# Tortilla.net
KiCad netlist of a schematic drawn in EAGLE
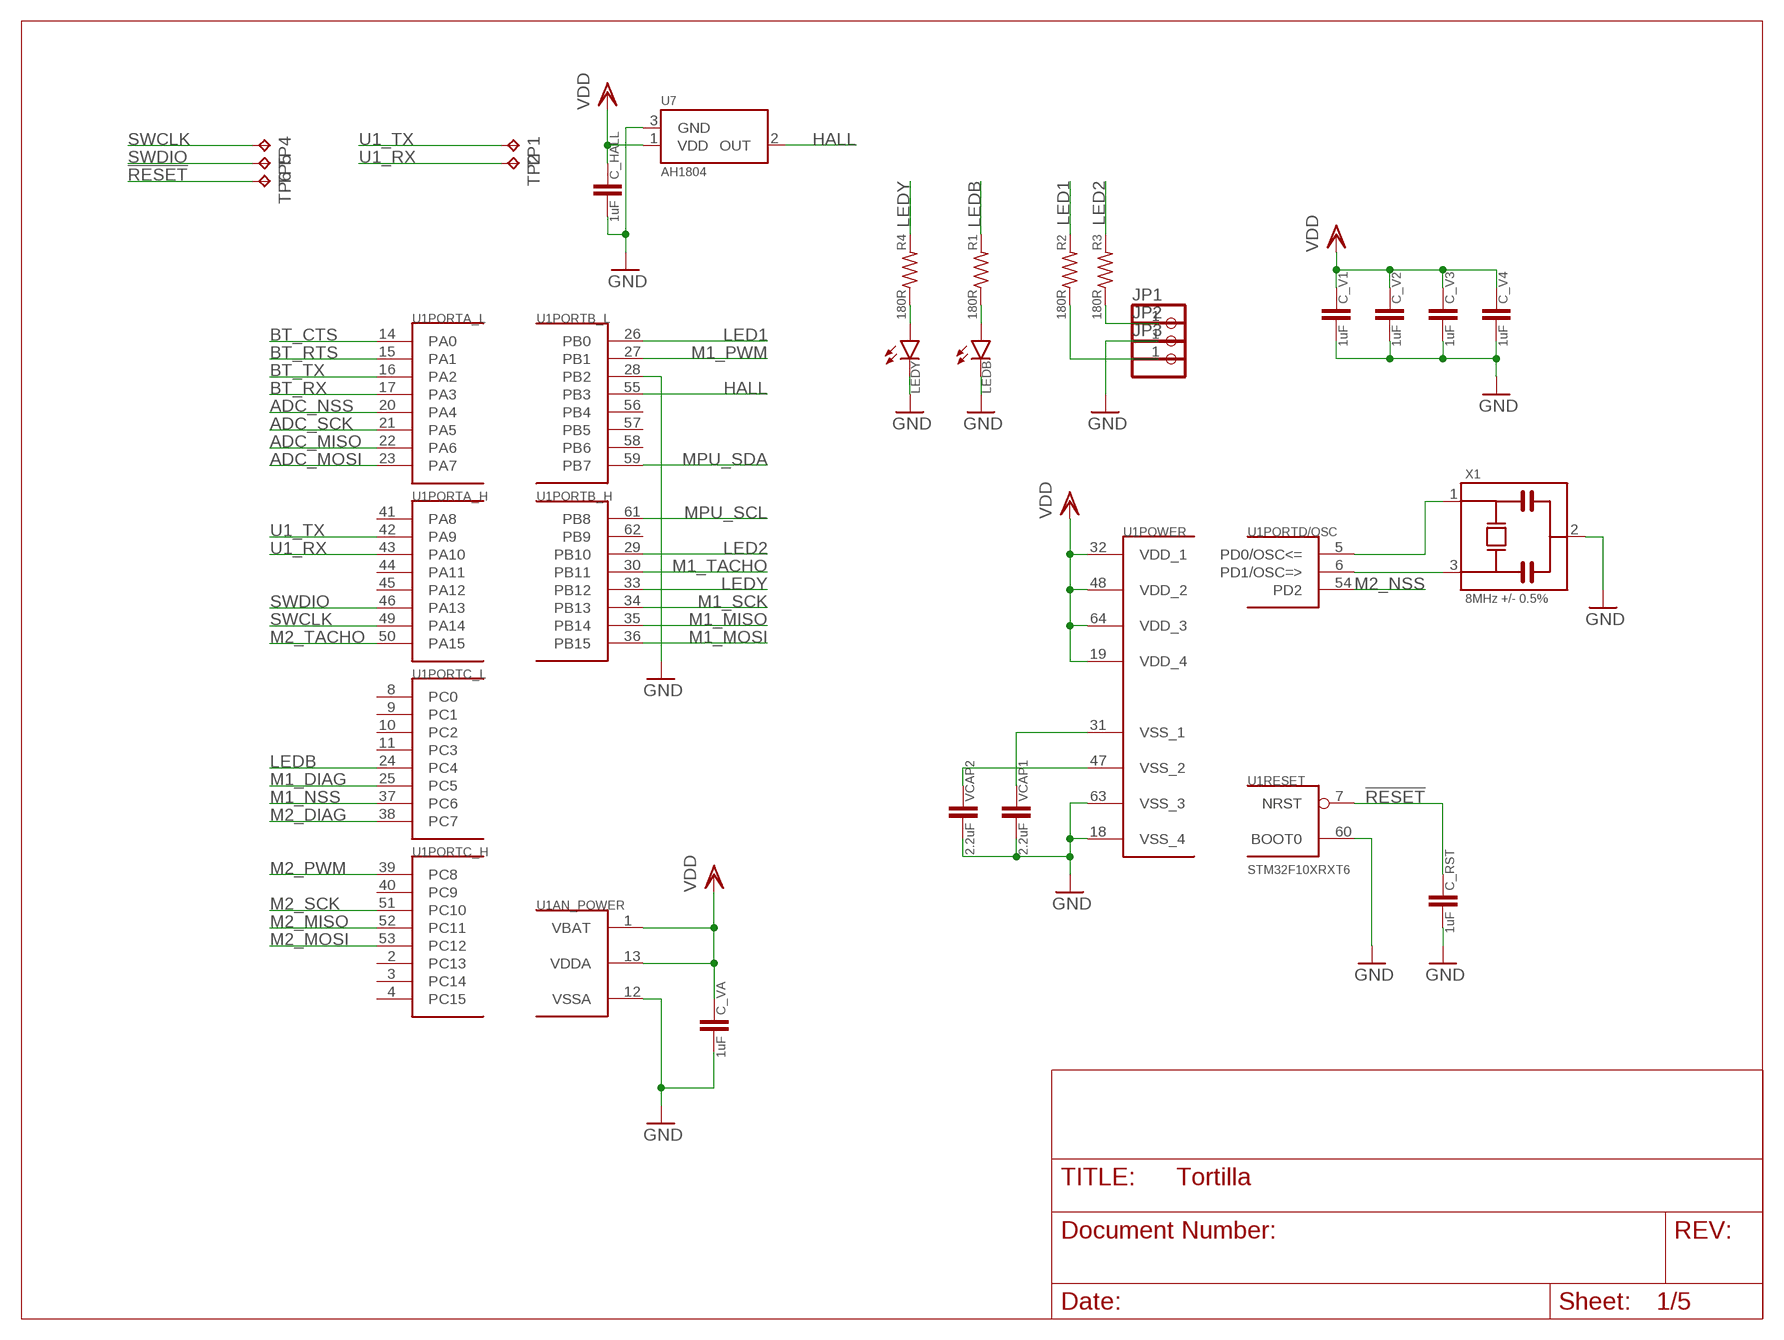
[diagram p0: schematic, sheet 1]
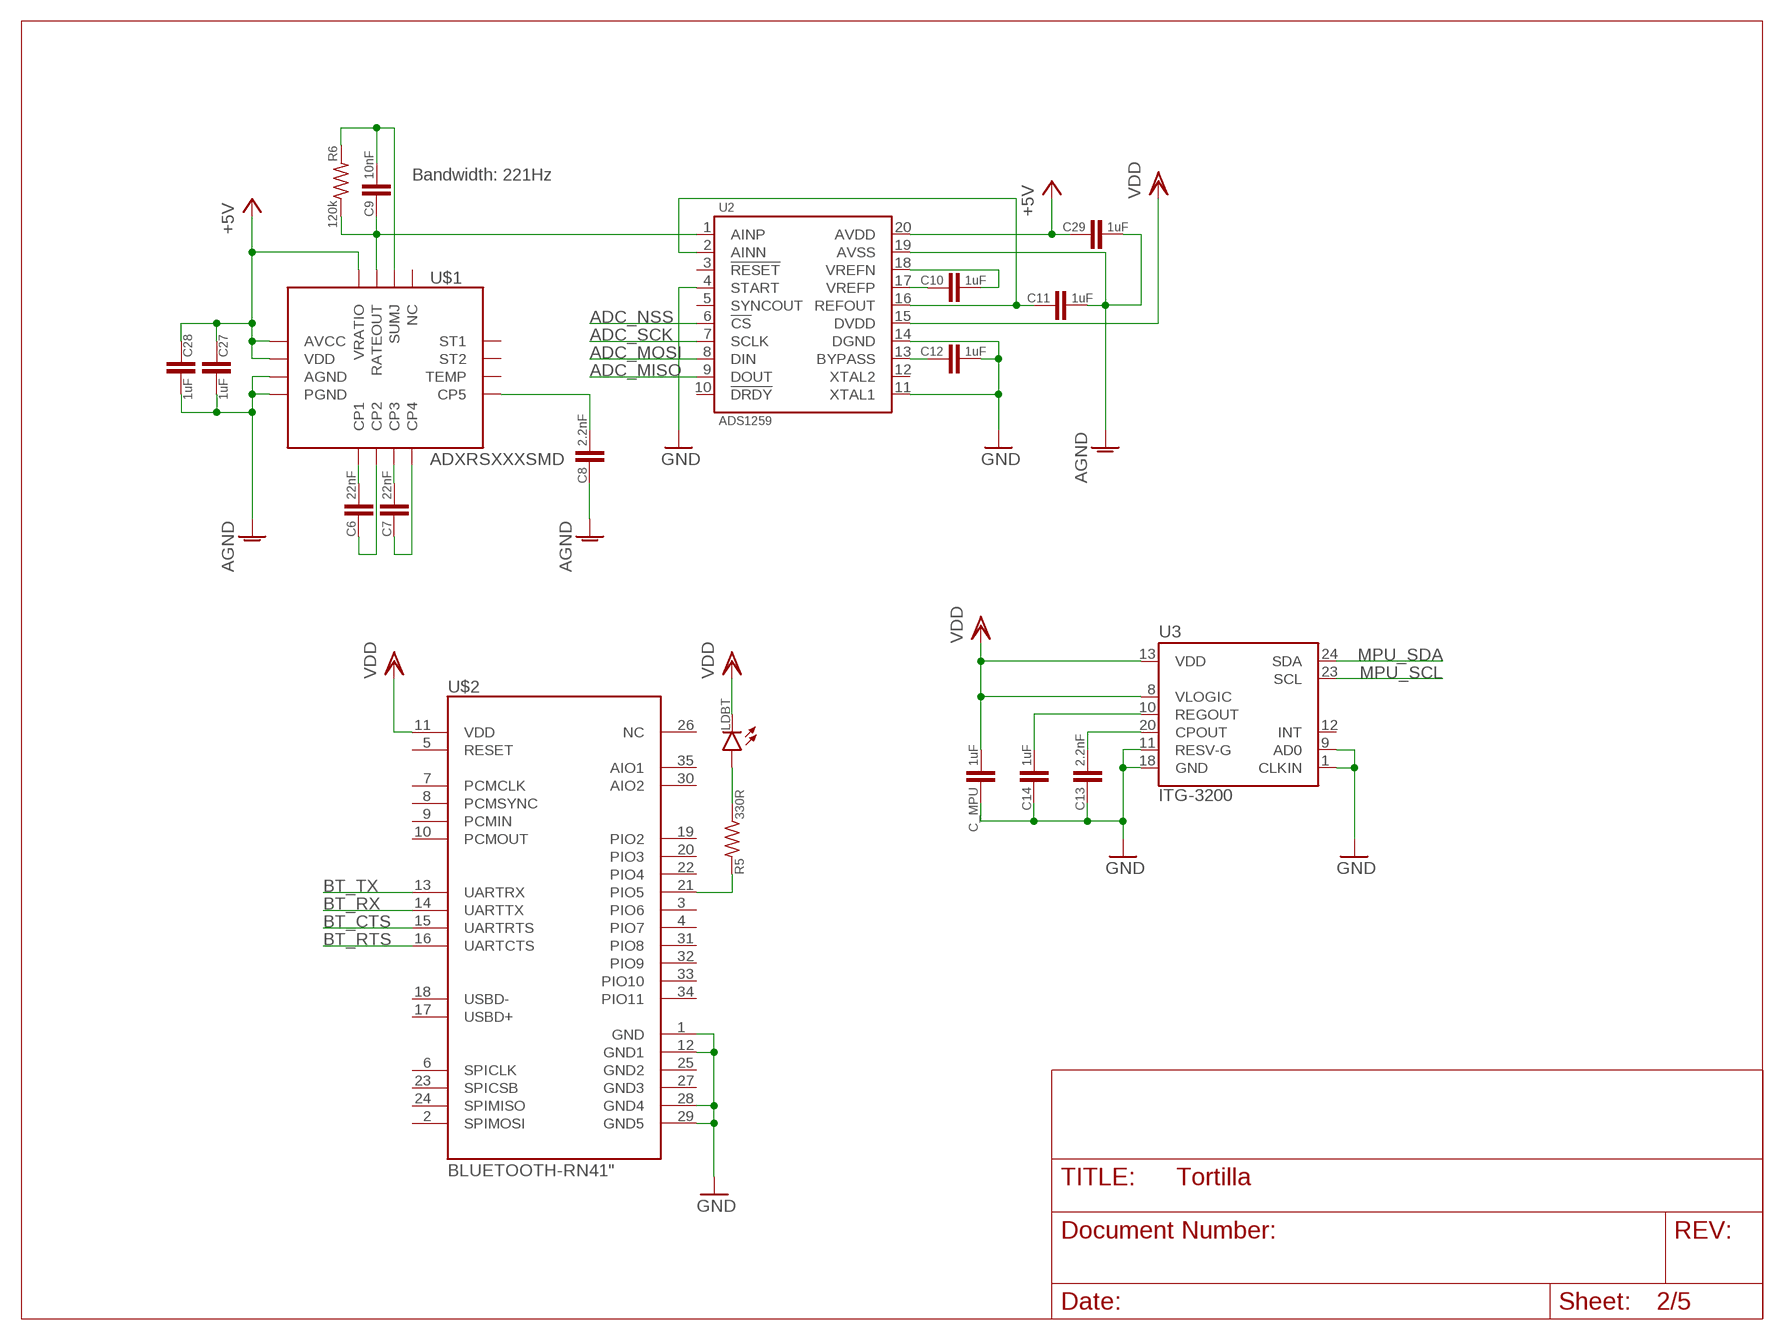
[diagram p1: schematic, sheet 2]
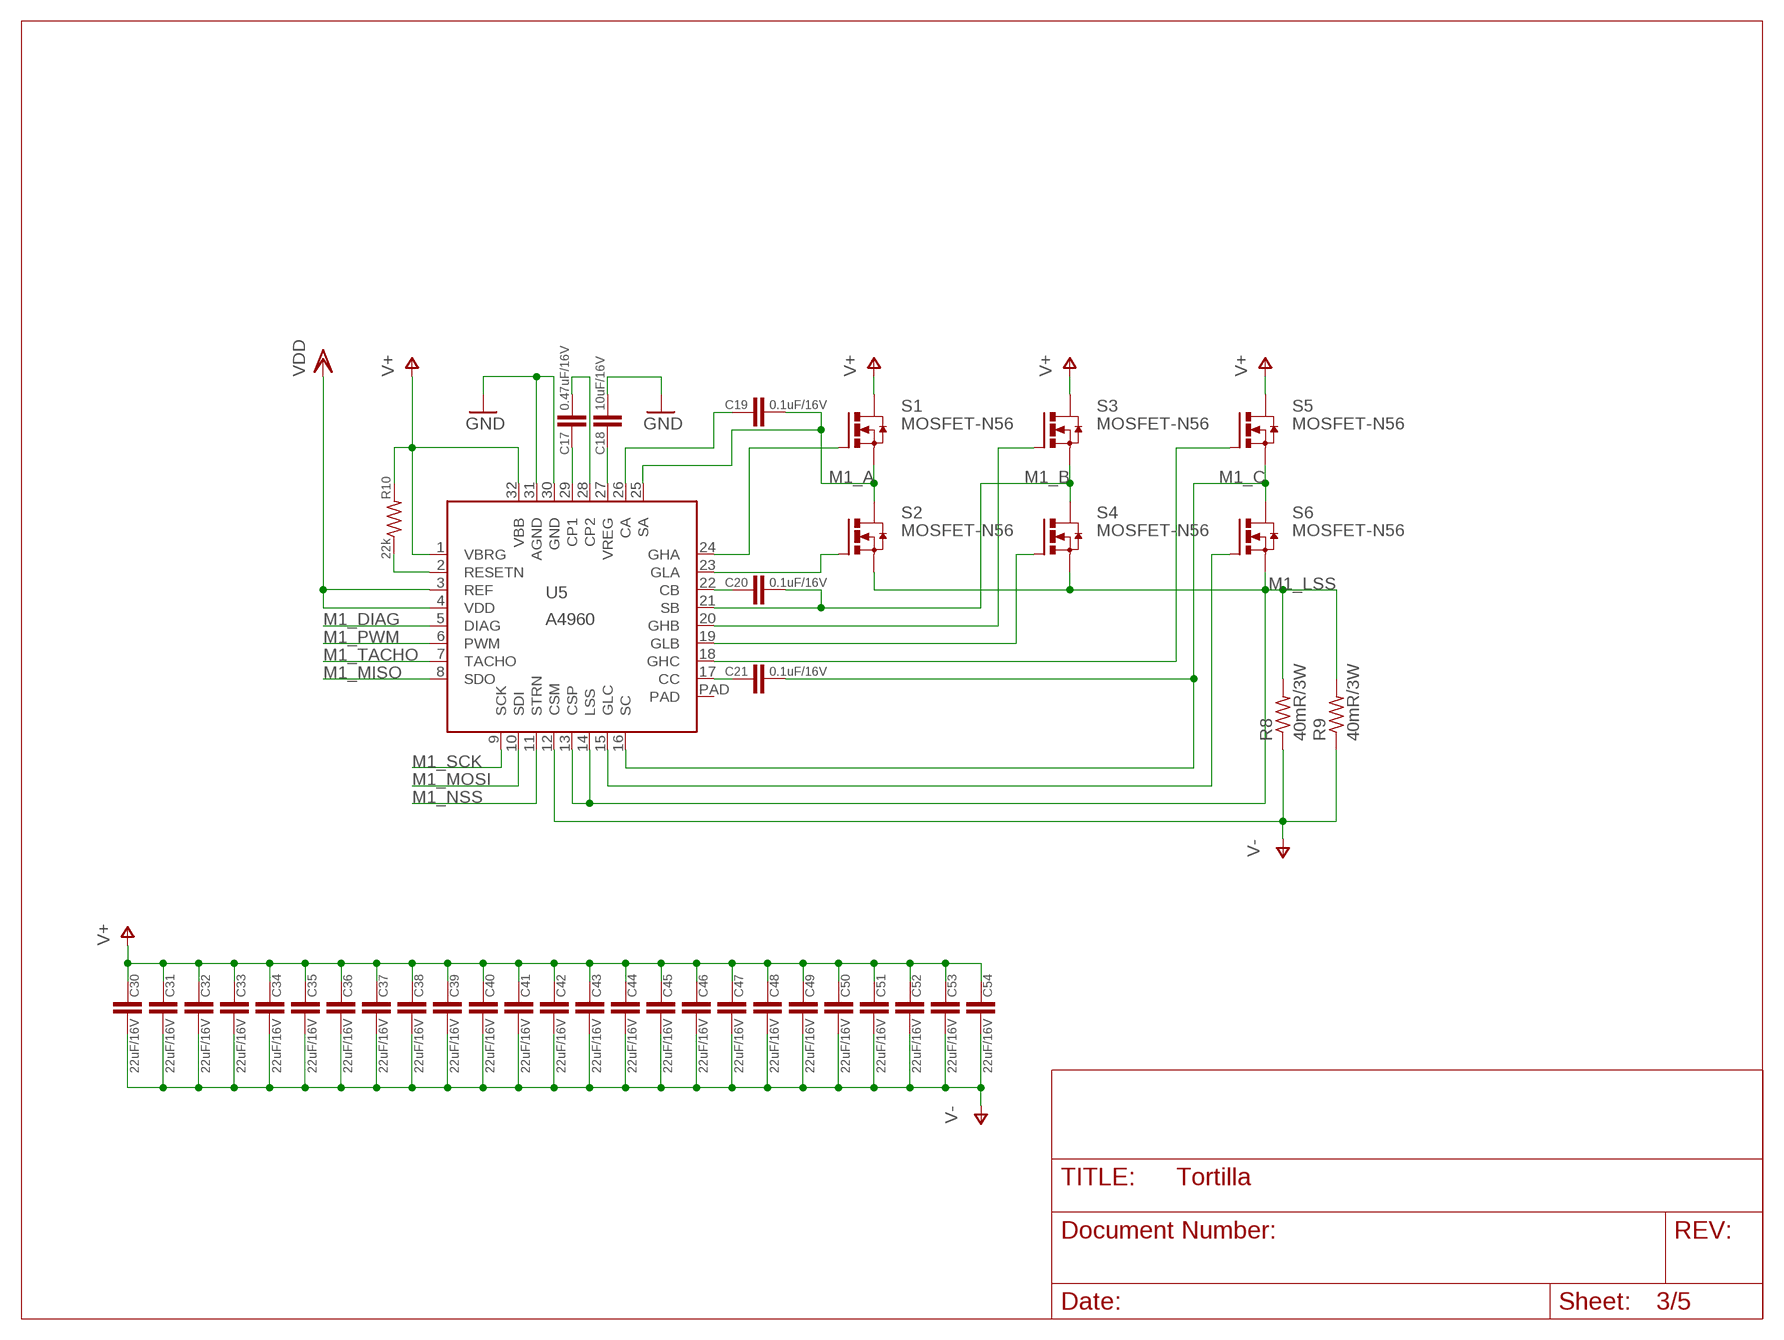
[diagram p2: schematic, sheet 3]
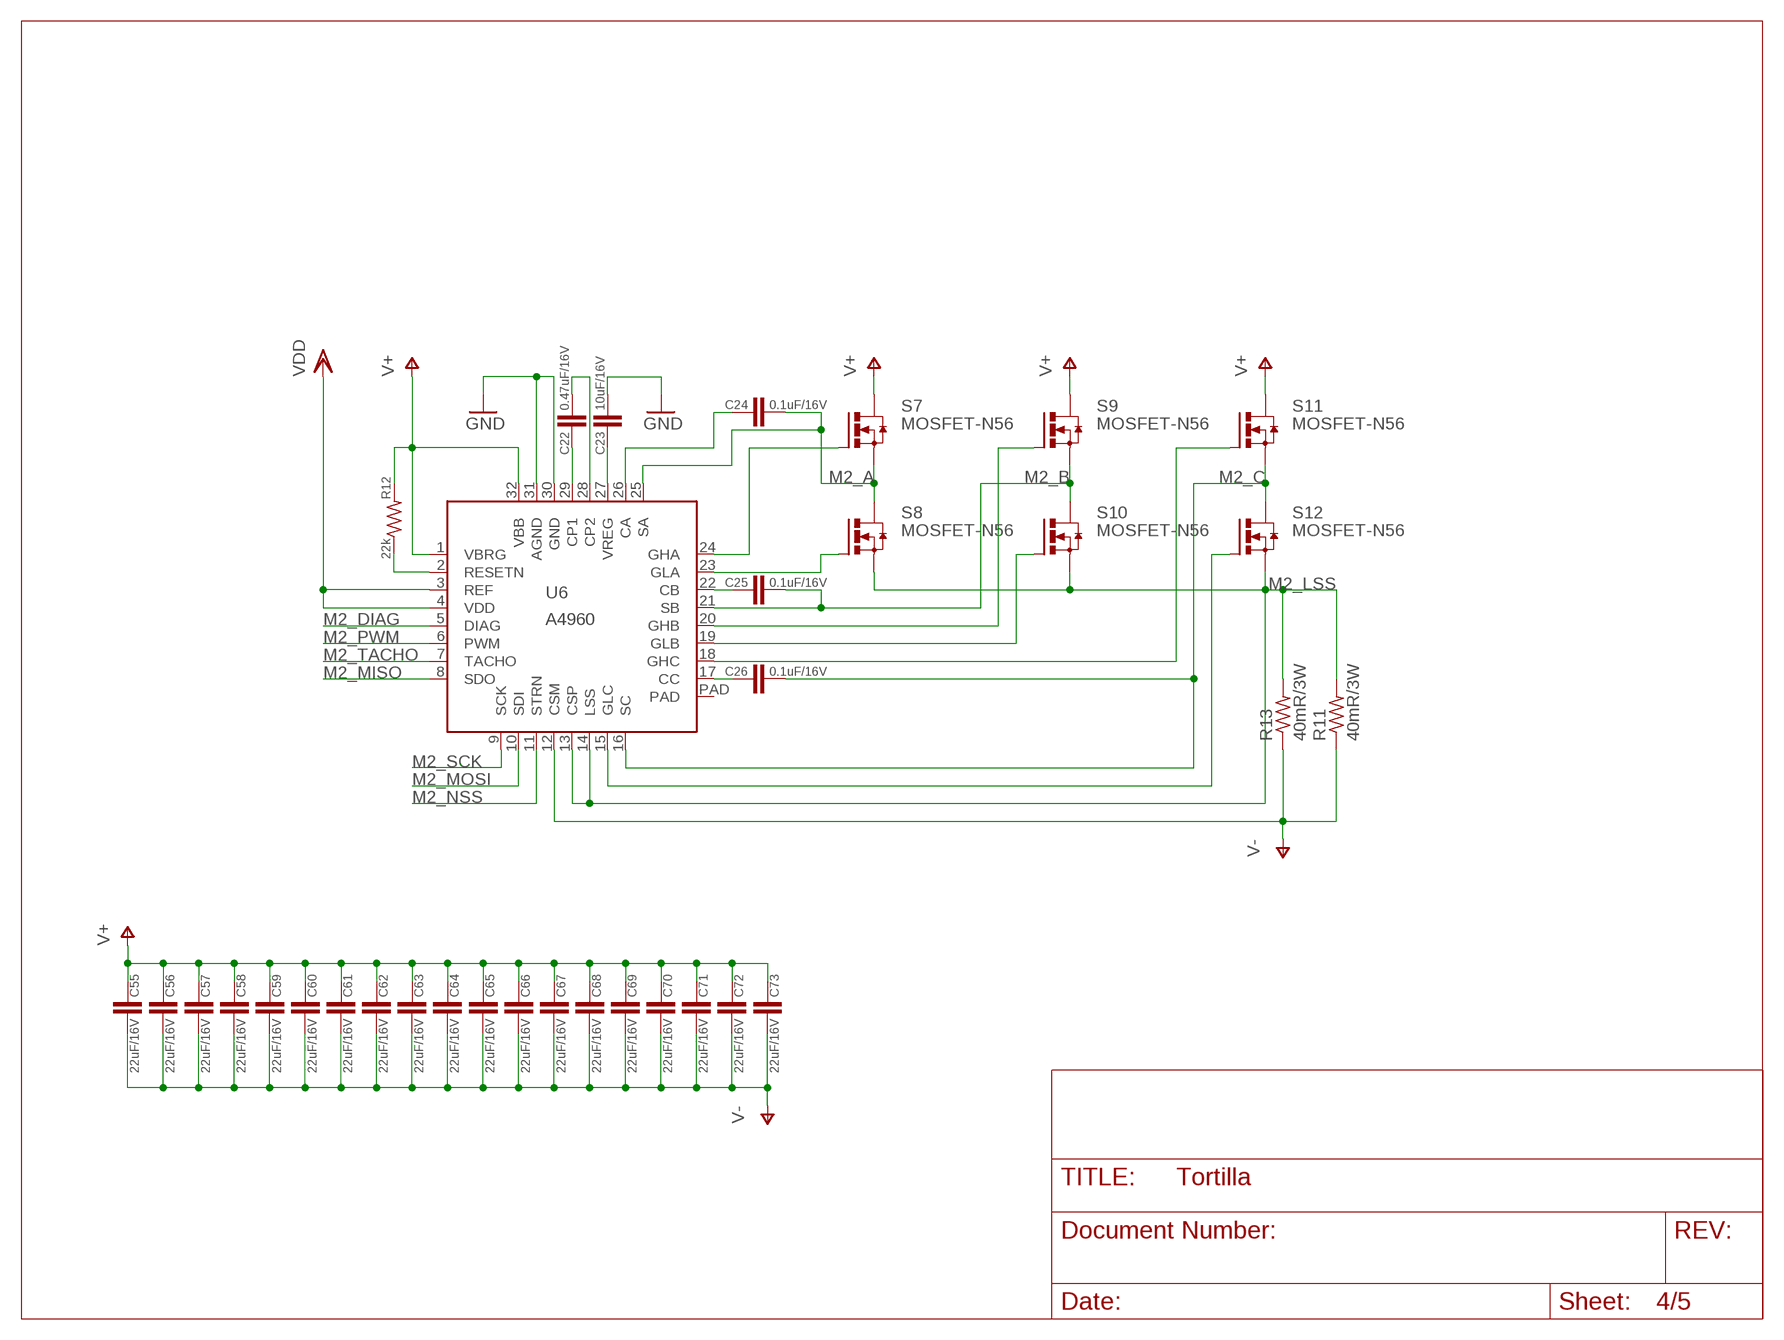
[diagram p3: schematic, sheet 4]
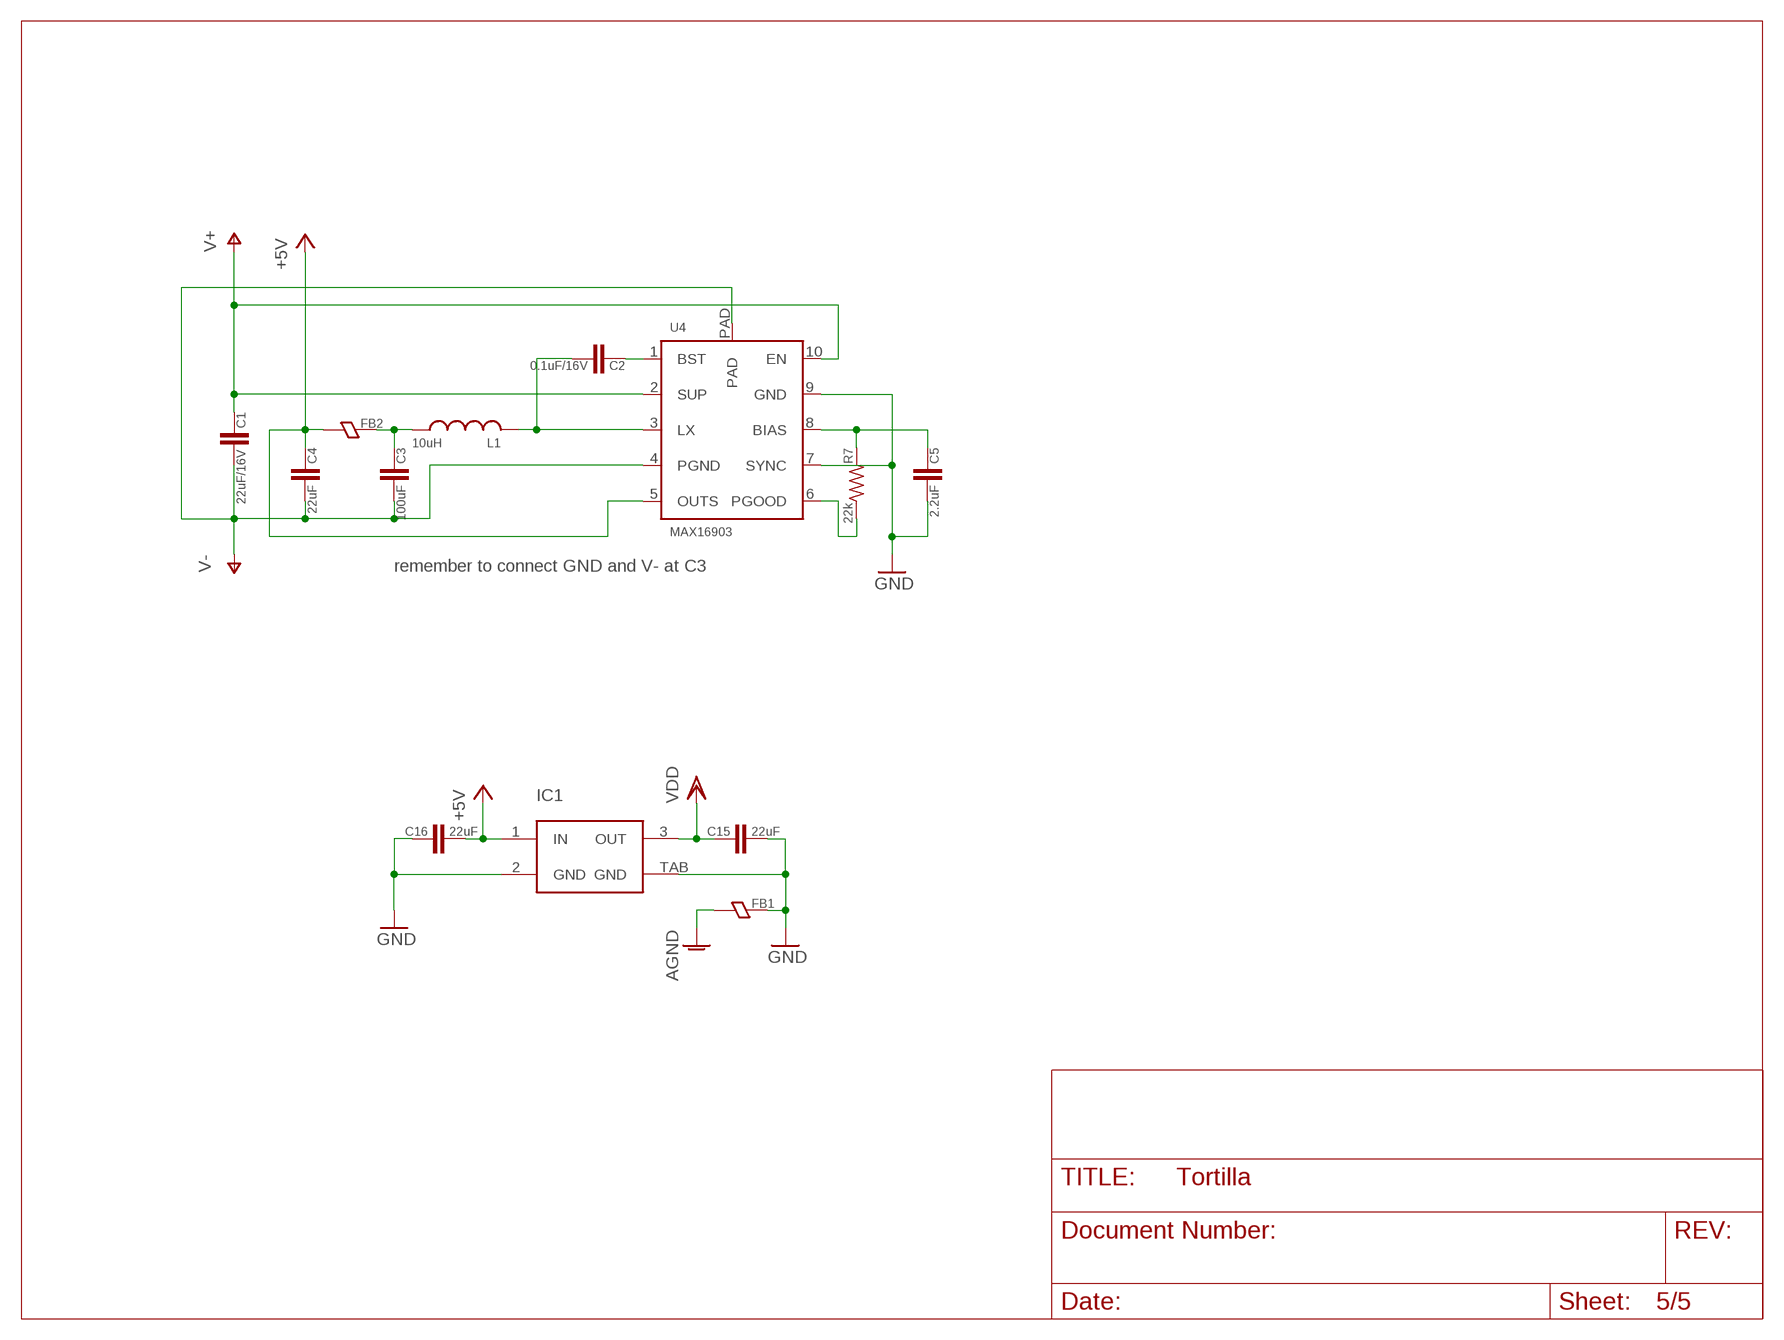
[diagram p4: schematic, sheet 5]

(export (version "E")
  (design (tool "Eeschema 10.0.6"))
  (components
    (comp (ref "C1")
      (value "22uF/16V")
      (footprint "eagle-import:0805")
      (libsource (lib "eagle-import") (part "C0805"))
    )
    (comp (ref "C2")
      (value "0.1uF/16V")
      (footprint "eagle-import:0603")
      (libsource (lib "eagle-import") (part "C0603"))
    )
    (comp (ref "C3")
      (value "100uF")
      (footprint "eagle-import:1206")
      (libsource (lib "eagle-import") (part "C1206"))
    )
    (comp (ref "C4")
      (value "22uF")
      (footprint "eagle-import:0805")
      (libsource (lib "eagle-import") (part "C0805"))
    )
    (comp (ref "C5")
      (value "2.2uF")
      (footprint "eagle-import:0603")
      (libsource (lib "eagle-import") (part "C0603"))
    )
    (comp (ref "C15")
      (value "22uF")
      (footprint "eagle-import:0805")
      (libsource (lib "eagle-import") (part "C0805"))
    )
    (comp (ref "C16")
      (value "22uF")
      (footprint "eagle-import:0805")
      (libsource (lib "eagle-import") (part "C0805"))
    )
    (comp (ref "FB1")
      (value "FERRITE0603")
      (footprint "eagle-import:0603")
      (libsource (lib "eagle-import") (part "FERRITE0603"))
    )
    (comp (ref "FB2")
      (value "FERRITE0603")
      (footprint "eagle-import:0603")
      (libsource (lib "eagle-import") (part "FERRITE0603"))
    )
    (comp (ref "IC1")
      (value "MCP1826S")
      (footprint "eagle-import:SOT223-3L")
      (libsource (lib "eagle-import") (part "MCP1826S"))
    )
    (comp (ref "L1")
      (value "10uH")
      (footprint "eagle-import:TAIYO-YUDEN_NR30")
      (libsource (lib "eagle-import") (part "L-US_NR30"))
    )
    (comp (ref "R7")
      (value "22k")
      (footprint "eagle-import:0603")
      (libsource (lib "eagle-import") (part "R0603"))
    )
    (comp (ref "U4")
      (value "MAX16903")
      (footprint "eagle-import:TDFN-10")
      (libsource (lib "eagle-import") (part "MAX16903"))
    )
    (comp (ref "C6")
      (value "22nF")
      (footprint "eagle-import:0603")
      (libsource (lib "eagle-import") (part "C0603"))
    )
    (comp (ref "C7")
      (value "22nF")
      (footprint "eagle-import:0603")
      (libsource (lib "eagle-import") (part "C0603"))
    )
    (comp (ref "C8")
      (value "2.2nF")
      (footprint "eagle-import:0603")
      (libsource (lib "eagle-import") (part "C0603"))
    )
    (comp (ref "C9")
      (value "10nF")
      (footprint "eagle-import:0603")
      (libsource (lib "eagle-import") (part "C0603"))
    )
    (comp (ref "C10")
      (value "1uF")
      (footprint "eagle-import:0603")
      (libsource (lib "eagle-import") (part "C0603"))
    )
    (comp (ref "C11")
      (value "1uF")
      (footprint "eagle-import:0603")
      (libsource (lib "eagle-import") (part "C0603"))
    )
    (comp (ref "C12")
      (value "1uF")
      (footprint "eagle-import:0603")
      (libsource (lib "eagle-import") (part "C0603"))
    )
    (comp (ref "C13")
      (value "2.2nF")
      (footprint "eagle-import:0603")
      (libsource (lib "eagle-import") (part "C0603"))
    )
    (comp (ref "C14")
      (value "1uF")
      (footprint "eagle-import:0603")
      (libsource (lib "eagle-import") (part "C0603"))
    )
    (comp (ref "C27")
      (value "1uF")
      (footprint "eagle-import:0603")
      (libsource (lib "eagle-import") (part "C0603"))
    )
    (comp (ref "C28")
      (value "1uF")
      (footprint "eagle-import:0603")
      (libsource (lib "eagle-import") (part "C0603"))
    )
    (comp (ref "C29")
      (value "1uF")
      (footprint "eagle-import:0603")
      (libsource (lib "eagle-import") (part "C0603"))
    )
    (comp (ref "C_MPU")
      (value "1uF")
      (footprint "eagle-import:0603")
      (libsource (lib "eagle-import") (part "C0603"))
    )
    (comp (ref "LDBT")
      (value "LED0805")
      (footprint "eagle-import:0805_POL")
      (libsource (lib "eagle-import") (part "LED0805"))
    )
    (comp (ref "R5")
      (value "330R")
      (footprint "eagle-import:0603")
      (libsource (lib "eagle-import") (part "R0603"))
    )
    (comp (ref "R6")
      (value "120k")
      (footprint "eagle-import:0603")
      (libsource (lib "eagle-import") (part "R0603"))
    )
    (comp (ref "U$1")
      (value "ADXRSXXXSMD")
      (footprint "eagle-import:BC-32")
      (libsource (lib "eagle-import") (part "ADXRSXXXSMD"))
    )
    (comp (ref "U$2")
      (value "BLUETOOTH-RN41\"")
      (footprint "eagle-import:RN41")
      (libsource (lib "eagle-import") (part "BLUETOOTH-RN41{dblquote}"))
    )
    (comp (ref "U2")
      (value "ADS1259")
      (footprint "eagle-import:TSSOP-20")
      (libsource (lib "eagle-import") (part "ADS1259"))
    )
    (comp (ref "U3")
      (value "ITG-3200")
      (footprint "eagle-import:QFN-24")
      (libsource (lib "eagle-import") (part "ITG-3200"))
    )
    (comp (ref "C22")
      (value "0.47uF/16V")
      (footprint "eagle-import:0603")
      (libsource (lib "eagle-import") (part "C0603"))
    )
    (comp (ref "C23")
      (value "10uF/16V")
      (footprint "eagle-import:0805")
      (libsource (lib "eagle-import") (part "C0805"))
    )
    (comp (ref "C24")
      (value "0.1uF/16V")
      (footprint "eagle-import:0603")
      (libsource (lib "eagle-import") (part "C0603"))
    )
    (comp (ref "C25")
      (value "0.1uF/16V")
      (footprint "eagle-import:0603")
      (libsource (lib "eagle-import") (part "C0603"))
    )
    (comp (ref "C26")
      (value "0.1uF/16V")
      (footprint "eagle-import:0603")
      (libsource (lib "eagle-import") (part "C0603"))
    )
    (comp (ref "C55")
      (value "22uF/16V")
      (footprint "eagle-import:1206")
      (libsource (lib "eagle-import") (part "C1206"))
    )
    (comp (ref "C56")
      (value "22uF/16V")
      (footprint "eagle-import:1206")
      (libsource (lib "eagle-import") (part "C1206"))
    )
    (comp (ref "C57")
      (value "22uF/16V")
      (footprint "eagle-import:1206")
      (libsource (lib "eagle-import") (part "C1206"))
    )
    (comp (ref "C58")
      (value "22uF/16V")
      (footprint "eagle-import:1206")
      (libsource (lib "eagle-import") (part "C1206"))
    )
    (comp (ref "C59")
      (value "22uF/16V")
      (footprint "eagle-import:1206")
      (libsource (lib "eagle-import") (part "C1206"))
    )
    (comp (ref "C60")
      (value "22uF/16V")
      (footprint "eagle-import:1206")
      (libsource (lib "eagle-import") (part "C1206"))
    )
    (comp (ref "C61")
      (value "22uF/16V")
      (footprint "eagle-import:1206")
      (libsource (lib "eagle-import") (part "C1206"))
    )
    (comp (ref "C62")
      (value "22uF/16V")
      (footprint "eagle-import:1206")
      (libsource (lib "eagle-import") (part "C1206"))
    )
    (comp (ref "C63")
      (value "22uF/16V")
      (footprint "eagle-import:1206")
      (libsource (lib "eagle-import") (part "C1206"))
    )
    (comp (ref "C64")
      (value "22uF/16V")
      (footprint "eagle-import:1206")
      (libsource (lib "eagle-import") (part "C1206"))
    )
    (comp (ref "C65")
      (value "22uF/16V")
      (footprint "eagle-import:1206")
      (libsource (lib "eagle-import") (part "C1206"))
    )
    (comp (ref "C66")
      (value "22uF/16V")
      (footprint "eagle-import:1206")
      (libsource (lib "eagle-import") (part "C1206"))
    )
    (comp (ref "C67")
      (value "22uF/16V")
      (footprint "eagle-import:1206")
      (libsource (lib "eagle-import") (part "C1206"))
    )
    (comp (ref "C68")
      (value "22uF/16V")
      (footprint "eagle-import:1206")
      (libsource (lib "eagle-import") (part "C1206"))
    )
    (comp (ref "C69")
      (value "22uF/16V")
      (footprint "eagle-import:1206")
      (libsource (lib "eagle-import") (part "C1206"))
    )
    (comp (ref "C70")
      (value "22uF/16V")
      (footprint "eagle-import:1206")
      (libsource (lib "eagle-import") (part "C1206"))
    )
    (comp (ref "C71")
      (value "22uF/16V")
      (footprint "eagle-import:1206")
      (libsource (lib "eagle-import") (part "C1206"))
    )
    (comp (ref "C72")
      (value "22uF/16V")
      (footprint "eagle-import:1206")
      (libsource (lib "eagle-import") (part "C1206"))
    )
    (comp (ref "C73")
      (value "22uF/16V")
      (footprint "eagle-import:1206")
      (libsource (lib "eagle-import") (part "C1206"))
    )
    (comp (ref "R11")
      (value "40mR/3W")
      (footprint "eagle-import:R2512")
      (libsource (lib "eagle-import") (part "R-US_R2512"))
    )
    (comp (ref "R12")
      (value "22k")
      (footprint "eagle-import:0603")
      (libsource (lib "eagle-import") (part "R0603"))
    )
    (comp (ref "R13")
      (value "40mR/3W")
      (footprint "eagle-import:R2512")
      (libsource (lib "eagle-import") (part "R-US_R2512"))
    )
    (comp (ref "S7")
      (value "MOSFET-N56")
      (footprint "eagle-import:SON-5X6")
      (libsource (lib "eagle-import") (part "MOSFET-N56"))
    )
    (comp (ref "S8")
      (value "MOSFET-N56")
      (footprint "eagle-import:SON-5X6")
      (libsource (lib "eagle-import") (part "MOSFET-N56"))
    )
    (comp (ref "S9")
      (value "MOSFET-N56")
      (footprint "eagle-import:SON-5X6")
      (libsource (lib "eagle-import") (part "MOSFET-N56"))
    )
    (comp (ref "S10")
      (value "MOSFET-N56")
      (footprint "eagle-import:SON-5X6")
      (libsource (lib "eagle-import") (part "MOSFET-N56"))
    )
    (comp (ref "S11")
      (value "MOSFET-N56")
      (footprint "eagle-import:SON-5X6")
      (libsource (lib "eagle-import") (part "MOSFET-N56"))
    )
    (comp (ref "S12")
      (value "MOSFET-N56")
      (footprint "eagle-import:SON-5X6")
      (libsource (lib "eagle-import") (part "MOSFET-N56"))
    )
    (comp (ref "U6")
      (value "A4960")
      (footprint "eagle-import:LQFP32-THERMPAD")
      (libsource (lib "eagle-import") (part "A4960"))
    )
    (comp (ref "C17")
      (value "0.47uF/16V")
      (footprint "eagle-import:0603")
      (libsource (lib "eagle-import") (part "C0603"))
    )
    (comp (ref "C18")
      (value "10uF/16V")
      (footprint "eagle-import:0805")
      (libsource (lib "eagle-import") (part "C0805"))
    )
    (comp (ref "C19")
      (value "0.1uF/16V")
      (footprint "eagle-import:0603")
      (libsource (lib "eagle-import") (part "C0603"))
    )
    (comp (ref "C20")
      (value "0.1uF/16V")
      (footprint "eagle-import:0603")
      (libsource (lib "eagle-import") (part "C0603"))
    )
    (comp (ref "C21")
      (value "0.1uF/16V")
      (footprint "eagle-import:0603")
      (libsource (lib "eagle-import") (part "C0603"))
    )
    (comp (ref "C30")
      (value "22uF/16V")
      (footprint "eagle-import:1206")
      (libsource (lib "eagle-import") (part "C1206"))
    )
    (comp (ref "C31")
      (value "22uF/16V")
      (footprint "eagle-import:1206")
      (libsource (lib "eagle-import") (part "C1206"))
    )
    (comp (ref "C32")
      (value "22uF/16V")
      (footprint "eagle-import:1206")
      (libsource (lib "eagle-import") (part "C1206"))
    )
    (comp (ref "C33")
      (value "22uF/16V")
      (footprint "eagle-import:1206")
      (libsource (lib "eagle-import") (part "C1206"))
    )
    (comp (ref "C34")
      (value "22uF/16V")
      (footprint "eagle-import:1206")
      (libsource (lib "eagle-import") (part "C1206"))
    )
    (comp (ref "C35")
      (value "22uF/16V")
      (footprint "eagle-import:1206")
      (libsource (lib "eagle-import") (part "C1206"))
    )
    (comp (ref "C36")
      (value "22uF/16V")
      (footprint "eagle-import:1206")
      (libsource (lib "eagle-import") (part "C1206"))
    )
    (comp (ref "C37")
      (value "22uF/16V")
      (footprint "eagle-import:1206")
      (libsource (lib "eagle-import") (part "C1206"))
    )
    (comp (ref "C38")
      (value "22uF/16V")
      (footprint "eagle-import:1206")
      (libsource (lib "eagle-import") (part "C1206"))
    )
    (comp (ref "C39")
      (value "22uF/16V")
      (footprint "eagle-import:1206")
      (libsource (lib "eagle-import") (part "C1206"))
    )
    (comp (ref "C40")
      (value "22uF/16V")
      (footprint "eagle-import:1206")
      (libsource (lib "eagle-import") (part "C1206"))
    )
    (comp (ref "C41")
      (value "22uF/16V")
      (footprint "eagle-import:1206")
      (libsource (lib "eagle-import") (part "C1206"))
    )
    (comp (ref "C42")
      (value "22uF/16V")
      (footprint "eagle-import:1206")
      (libsource (lib "eagle-import") (part "C1206"))
    )
    (comp (ref "C43")
      (value "22uF/16V")
      (footprint "eagle-import:1206")
      (libsource (lib "eagle-import") (part "C1206"))
    )
    (comp (ref "C44")
      (value "22uF/16V")
      (footprint "eagle-import:1206")
      (libsource (lib "eagle-import") (part "C1206"))
    )
    (comp (ref "C45")
      (value "22uF/16V")
      (footprint "eagle-import:1206")
      (libsource (lib "eagle-import") (part "C1206"))
    )
    (comp (ref "C46")
      (value "22uF/16V")
      (footprint "eagle-import:1206")
      (libsource (lib "eagle-import") (part "C1206"))
    )
    (comp (ref "C47")
      (value "22uF/16V")
      (footprint "eagle-import:1206")
      (libsource (lib "eagle-import") (part "C1206"))
    )
    (comp (ref "C48")
      (value "22uF/16V")
      (footprint "eagle-import:1206")
      (libsource (lib "eagle-import") (part "C1206"))
    )
    (comp (ref "C49")
      (value "22uF/16V")
      (footprint "eagle-import:1206")
      (libsource (lib "eagle-import") (part "C1206"))
    )
    (comp (ref "C50")
      (value "22uF/16V")
      (footprint "eagle-import:1206")
      (libsource (lib "eagle-import") (part "C1206"))
    )
    (comp (ref "C51")
      (value "22uF/16V")
      (footprint "eagle-import:1206")
      (libsource (lib "eagle-import") (part "C1206"))
    )
    (comp (ref "C52")
      (value "22uF/16V")
      (footprint "eagle-import:1206")
      (libsource (lib "eagle-import") (part "C1206"))
    )
    (comp (ref "C53")
      (value "22uF/16V")
      (footprint "eagle-import:1206")
      (libsource (lib "eagle-import") (part "C1206"))
    )
    (comp (ref "C54")
      (value "22uF/16V")
      (footprint "eagle-import:1206")
      (libsource (lib "eagle-import") (part "C1206"))
    )
    (comp (ref "R8")
      (value "40mR/3W")
      (footprint "eagle-import:R2512")
      (libsource (lib "eagle-import") (part "R-US_R2512"))
    )
    (comp (ref "R9")
      (value "40mR/3W")
      (footprint "eagle-import:R2512")
      (libsource (lib "eagle-import") (part "R-US_R2512"))
    )
    (comp (ref "R10")
      (value "22k")
      (footprint "eagle-import:0603")
      (libsource (lib "eagle-import") (part "R0603"))
    )
    (comp (ref "S1")
      (value "MOSFET-N56")
      (footprint "eagle-import:SON-5X6")
      (libsource (lib "eagle-import") (part "MOSFET-N56"))
    )
    (comp (ref "S2")
      (value "MOSFET-N56")
      (footprint "eagle-import:SON-5X6")
      (libsource (lib "eagle-import") (part "MOSFET-N56"))
    )
    (comp (ref "S3")
      (value "MOSFET-N56")
      (footprint "eagle-import:SON-5X6")
      (libsource (lib "eagle-import") (part "MOSFET-N56"))
    )
    (comp (ref "S4")
      (value "MOSFET-N56")
      (footprint "eagle-import:SON-5X6")
      (libsource (lib "eagle-import") (part "MOSFET-N56"))
    )
    (comp (ref "S5")
      (value "MOSFET-N56")
      (footprint "eagle-import:SON-5X6")
      (libsource (lib "eagle-import") (part "MOSFET-N56"))
    )
    (comp (ref "S6")
      (value "MOSFET-N56")
      (footprint "eagle-import:SON-5X6")
      (libsource (lib "eagle-import") (part "MOSFET-N56"))
    )
    (comp (ref "U5")
      (value "A4960")
      (footprint "eagle-import:LQFP32-THERMPAD")
      (libsource (lib "eagle-import") (part "A4960"))
    )
    (comp (ref "C_HALL")
      (value "1uF")
      (footprint "eagle-import:0603")
      (libsource (lib "eagle-import") (part "C0603"))
    )
    (comp (ref "C_RST")
      (value "1uF")
      (footprint "eagle-import:0603")
      (libsource (lib "eagle-import") (part "C0603"))
    )
    (comp (ref "C_V1")
      (value "1uF")
      (footprint "eagle-import:0603")
      (libsource (lib "eagle-import") (part "C0603"))
    )
    (comp (ref "C_V2")
      (value "1uF")
      (footprint "eagle-import:0603")
      (libsource (lib "eagle-import") (part "C0603"))
    )
    (comp (ref "C_V3")
      (value "1uF")
      (footprint "eagle-import:0603")
      (libsource (lib "eagle-import") (part "C0603"))
    )
    (comp (ref "C_V4")
      (value "1uF")
      (footprint "eagle-import:0603")
      (libsource (lib "eagle-import") (part "C0603"))
    )
    (comp (ref "C_VA")
      (value "1uF")
      (footprint "eagle-import:0603")
      (libsource (lib "eagle-import") (part "C0603"))
    )
    (comp (ref "JP1")
      (value "PINHD-1X1")
      (footprint "eagle-import:1X01")
      (libsource (lib "eagle-import") (part "PINHD-1X1"))
    )
    (comp (ref "JP2")
      (value "PINHD-1X1")
      (footprint "eagle-import:1X01")
      (libsource (lib "eagle-import") (part "PINHD-1X1"))
    )
    (comp (ref "JP3")
      (value "PINHD-1X1")
      (footprint "eagle-import:1X01")
      (libsource (lib "eagle-import") (part "PINHD-1X1"))
    )
    (comp (ref "LEDB")
      (value "LED0805")
      (footprint "eagle-import:0805_POL")
      (libsource (lib "eagle-import") (part "LED0805"))
    )
    (comp (ref "LEDY")
      (value "LED0805")
      (footprint "eagle-import:0805_POL")
      (libsource (lib "eagle-import") (part "LED0805"))
    )
    (comp (ref "R1")
      (value "180R")
      (footprint "eagle-import:0603")
      (libsource (lib "eagle-import") (part "R0603"))
    )
    (comp (ref "R2")
      (value "180R")
      (footprint "eagle-import:0603")
      (libsource (lib "eagle-import") (part "R0603"))
    )
    (comp (ref "R3")
      (value "180R")
      (footprint "eagle-import:0603")
      (libsource (lib "eagle-import") (part "R0603"))
    )
    (comp (ref "R4")
      (value "180R")
      (footprint "eagle-import:0603")
      (libsource (lib "eagle-import") (part "R0603"))
    )
    (comp (ref "TP1")
      (value "TPB1,27")
      (footprint "eagle-import:B1,27")
      (libsource (lib "eagle-import") (part "TPB1,27"))
    )
    (comp (ref "TP2")
      (value "TPB1,27")
      (footprint "eagle-import:B1,27")
      (libsource (lib "eagle-import") (part "TPB1,27"))
    )
    (comp (ref "TP4")
      (value "TPB1,27")
      (footprint "eagle-import:B1,27")
      (libsource (lib "eagle-import") (part "TPB1,27"))
    )
    (comp (ref "TP5")
      (value "TPB1,27")
      (footprint "eagle-import:B1,27")
      (libsource (lib "eagle-import") (part "TPB1,27"))
    )
    (comp (ref "TP6")
      (value "TPB1,27")
      (footprint "eagle-import:B1,27")
      (libsource (lib "eagle-import") (part "TPB1,27"))
    )
    (comp (ref "U1")
      (value "STM32F10XRXT6")
      (footprint "eagle-import:TQFP64")
      (libsource (lib "eagle-import") (part "STM32F10XRXT6"))
    )
    (comp (ref "U7")
      (value "AH1804")
      (footprint "eagle-import:SOT23-3")
      (libsource (lib "eagle-import") (part "AH1804"))
    )
    (comp (ref "VCAP1")
      (value "2.2uF")
      (footprint "eagle-import:0603")
      (libsource (lib "eagle-import") (part "C0603"))
    )
    (comp (ref "VCAP2")
      (value "2.2uF")
      (footprint "eagle-import:0603")
      (libsource (lib "eagle-import") (part "C0603"))
    )
    (comp (ref "X1")
      (value "8MHz +/- 0.5%")
      (footprint "eagle-import:MURATA_CSTCE")
      (libsource (lib "eagle-import") (part "MURATA_CSTCE"))
    )
  )
  (nets
    (net (code "1") (name "+5V") (class "Default")
      (node (ref "C16") (pin "2") (pinfunction "2_2") (pintype "passive"))
      (node (ref "C27") (pin "1") (pinfunction "1_1") (pintype "passive"))
      (node (ref "C28") (pin "1") (pinfunction "1_1") (pintype "passive"))
      (node (ref "C29") (pin "1") (pinfunction "1_1") (pintype "passive"))
      (node (ref "C4") (pin "1") (pinfunction "1_1") (pintype "passive"))
      (node (ref "FB2") (pin "1") (pinfunction "1_1") (pintype "passive"))
      (node (ref "IC1") (pin "1") (pinfunction "IN_1") (pintype "passive"))
      (node (ref "U$1") (pin "AVCC") (pinfunction "AVCC_AVCC") (pintype "bidirectional"))
      (node (ref "U$1") (pin "VDD") (pinfunction "VDD_VDD") (pintype "bidirectional"))
      (node (ref "U$1") (pin "VRATIO") (pinfunction "VRATIO_VRATIO") (pintype "bidirectional"))
      (node (ref "U2") (pin "20") (pinfunction "AVDD_20") (pintype "power_in"))
      (node (ref "U4") (pin "5") (pinfunction "OUTS_5") (pintype "bidirectional"))
    )
    (net (code "2") (name "ADC_MISO") (class "Default")
      (node (ref "U1") (pin "22") (pinfunction "PA6_22") (pintype "bidirectional"))
      (node (ref "U2") (pin "9") (pinfunction "DOUT_9") (pintype "output"))
    )
    (net (code "3") (name "ADC_MOSI") (class "Default")
      (node (ref "U1") (pin "23") (pinfunction "PA7_23") (pintype "bidirectional"))
      (node (ref "U2") (pin "8") (pinfunction "DIN_8") (pintype "input"))
    )
    (net (code "4") (name "ADC_NSS") (class "Default")
      (node (ref "U1") (pin "20") (pinfunction "PA4_20") (pintype "bidirectional"))
      (node (ref "U2") (pin "6") (pinfunction "~{CS}_6") (pintype "input"))
    )
    (net (code "5") (name "ADC_SCK") (class "Default")
      (node (ref "U1") (pin "21") (pinfunction "PA5_21") (pintype "bidirectional"))
      (node (ref "U2") (pin "7") (pinfunction "SCLK_7") (pintype "input"))
    )
    (net (code "6") (name "AGND") (class "Default")
      (node (ref "C11") (pin "2") (pinfunction "2_2") (pintype "passive"))
      (node (ref "C27") (pin "2") (pinfunction "2_2") (pintype "passive"))
      (node (ref "C28") (pin "2") (pinfunction "2_2") (pintype "passive"))
      (node (ref "C29") (pin "2") (pinfunction "2_2") (pintype "passive"))
      (node (ref "C8") (pin "1") (pinfunction "1_1") (pintype "passive"))
      (node (ref "FB1") (pin "1") (pinfunction "1_1") (pintype "passive"))
      (node (ref "U$1") (pin "AGND") (pinfunction "AGND_AGND") (pintype "bidirectional"))
      (node (ref "U$1") (pin "PGND") (pinfunction "PGND_PGND") (pintype "bidirectional"))
      (node (ref "U2") (pin "19") (pinfunction "AVSS_19") (pintype "power_in"))
    )
    (net (code "7") (name "BT_CTS") (class "Default")
      (node (ref "U$2") (pin "15") (pinfunction "UARTRTS_15") (pintype "bidirectional"))
      (node (ref "U1") (pin "14") (pinfunction "PA0_14") (pintype "bidirectional"))
    )
    (net (code "8") (name "BT_RTS") (class "Default")
      (node (ref "U$2") (pin "16") (pinfunction "UARTCTS_16") (pintype "bidirectional"))
      (node (ref "U1") (pin "15") (pinfunction "PA1_15") (pintype "bidirectional"))
    )
    (net (code "9") (name "BT_RX") (class "Default")
      (node (ref "U$2") (pin "14") (pinfunction "UARTTX_14") (pintype "bidirectional"))
      (node (ref "U1") (pin "17") (pinfunction "PA3_17") (pintype "bidirectional"))
    )
    (net (code "10") (name "BT_TX") (class "Default")
      (node (ref "U$2") (pin "13") (pinfunction "UARTRX_13") (pintype "bidirectional"))
      (node (ref "U1") (pin "16") (pinfunction "PA2_16") (pintype "bidirectional"))
    )
    (net (code "11") (name "GND") (class "Default")
      (node (ref "C12") (pin "2") (pinfunction "2_2") (pintype "passive"))
      (node (ref "C13") (pin "1") (pinfunction "1_1") (pintype "passive"))
      (node (ref "C14") (pin "1") (pinfunction "1_1") (pintype "passive"))
      (node (ref "C15") (pin "2") (pinfunction "2_2") (pintype "passive"))
      (node (ref "C16") (pin "1") (pinfunction "1_1") (pintype "passive"))
      (node (ref "C18") (pin "2") (pinfunction "2_2") (pintype "passive"))
      (node (ref "C23") (pin "2") (pinfunction "2_2") (pintype "passive"))
      (node (ref "C5") (pin "2") (pinfunction "2_2") (pintype "passive"))
      (node (ref "C_HALL") (pin "2") (pinfunction "2_2") (pintype "passive"))
      (node (ref "C_MPU") (pin "1") (pinfunction "1_1") (pintype "passive"))
      (node (ref "C_RST") (pin "2") (pinfunction "2_2") (pintype "passive"))
      (node (ref "C_V1") (pin "2") (pinfunction "2_2") (pintype "passive"))
      (node (ref "C_V2") (pin "2") (pinfunction "2_2") (pintype "passive"))
      (node (ref "C_V3") (pin "2") (pinfunction "2_2") (pintype "passive"))
      (node (ref "C_V4") (pin "2") (pinfunction "2_2") (pintype "passive"))
      (node (ref "C_VA") (pin "2") (pinfunction "2_2") (pintype "passive"))
      (node (ref "FB1") (pin "2") (pinfunction "2_2") (pintype "passive"))
      (node (ref "IC1") (pin "2") (pinfunction "GND_2") (pintype "passive"))
      (node (ref "IC1") (pin "TAB") (pinfunction "GND_TAB") (pintype "passive"))
      (node (ref "JP2") (pin "1") (pinfunction "1_1") (pintype "passive"))
      (node (ref "LEDB") (pin "-") (pinfunction "C_-") (pintype "passive"))
      (node (ref "LEDY") (pin "-") (pinfunction "C_-") (pintype "passive"))
      (node (ref "U$2") (pin "1") (pinfunction "GND_1") (pintype "bidirectional"))
      (node (ref "U$2") (pin "12") (pinfunction "GND1_12") (pintype "bidirectional"))
      (node (ref "U$2") (pin "28") (pinfunction "GND4_28") (pintype "bidirectional"))
      (node (ref "U$2") (pin "29") (pinfunction "GND5_29") (pintype "bidirectional"))
      (node (ref "U1") (pin "12") (pinfunction "VSSA_12") (pintype "power_in"))
      (node (ref "U1") (pin "18") (pinfunction "VSS_4_18") (pintype "power_in"))
      (node (ref "U1") (pin "28") (pinfunction "PB2_28") (pintype "bidirectional"))
      (node (ref "U1") (pin "60") (pinfunction "BOOT0_60") (pintype "input"))
      (node (ref "U1") (pin "63") (pinfunction "VSS_3_63") (pintype "power_in"))
      (node (ref "U2") (pin "11") (pinfunction "XTAL1_11") (pintype "bidirectional"))
      (node (ref "U2") (pin "14") (pinfunction "DGND_14") (pintype "power_in"))
      (node (ref "U2") (pin "4") (pinfunction "START_4") (pintype "input"))
      (node (ref "U3") (pin "1") (pinfunction "CLKIN_1") (pintype "bidirectional"))
      (node (ref "U3") (pin "11") (pinfunction "RESV-G_11") (pintype "bidirectional"))
      (node (ref "U3") (pin "18") (pinfunction "GND_18") (pintype "bidirectional"))
      (node (ref "U3") (pin "9") (pinfunction "AD0_9") (pintype "bidirectional"))
      (node (ref "U4") (pin "7") (pinfunction "SYNC_7") (pintype "bidirectional"))
      (node (ref "U4") (pin "9") (pinfunction "GND_9") (pintype "power_in"))
      (node (ref "U5") (pin "30") (pinfunction "GND_30") (pintype "power_in"))
      (node (ref "U5") (pin "31") (pinfunction "AGND_31") (pintype "power_in"))
      (node (ref "U6") (pin "30") (pinfunction "GND_30") (pintype "power_in"))
      (node (ref "U6") (pin "31") (pinfunction "AGND_31") (pintype "power_in"))
      (node (ref "U7") (pin "3") (pinfunction "GND_3") (pintype "power_in"))
      (node (ref "VCAP1") (pin "2") (pinfunction "2_2") (pintype "passive"))
      (node (ref "VCAP2") (pin "2") (pinfunction "2_2") (pintype "passive"))
      (node (ref "X1") (pin "2") (pinfunction "P$2_2") (pintype "bidirectional"))
    )
    (net (code "12") (name "HALL") (class "Default")
      (node (ref "U1") (pin "55") (pinfunction "PB3_55") (pintype "bidirectional"))
      (node (ref "U7") (pin "2") (pinfunction "OUT_2") (pintype "output"))
    )
    (net (code "13") (name "LED1") (class "Default")
      (node (ref "R2") (pin "2") (pinfunction "2_2") (pintype "passive"))
      (node (ref "U1") (pin "26") (pinfunction "PB0_26") (pintype "bidirectional"))
    )
    (net (code "14") (name "LED2") (class "Default")
      (node (ref "R3") (pin "2") (pinfunction "2_2") (pintype "passive"))
      (node (ref "U1") (pin "29") (pinfunction "PB10_29") (pintype "bidirectional"))
    )
    (net (code "15") (name "LEDB") (class "Default")
      (node (ref "R1") (pin "2") (pinfunction "2_2") (pintype "passive"))
      (node (ref "U1") (pin "24") (pinfunction "PC4_24") (pintype "bidirectional"))
    )
    (net (code "16") (name "LEDY") (class "Default")
      (node (ref "R4") (pin "2") (pinfunction "2_2") (pintype "passive"))
      (node (ref "U1") (pin "33") (pinfunction "PB12_33") (pintype "bidirectional"))
    )
    (net (code "17") (name "M1_A") (class "Default")
      (node (ref "C19") (pin "2") (pinfunction "2_2") (pintype "passive"))
      (node (ref "S1") (pin "S1") (pinfunction "S_S1") (pintype "passive"))
      (node (ref "S1") (pin "S2") (pinfunction "S_S2") (pintype "passive"))
      (node (ref "S1") (pin "S3") (pinfunction "S_S3") (pintype "passive"))
      (node (ref "S2") (pin "D") (pinfunction "D_D") (pintype "passive"))
      (node (ref "U5") (pin "25") (pinfunction "SA_25") (pintype "bidirectional"))
    )
    (net (code "18") (name "M1_B") (class "Default")
      (node (ref "C20") (pin "2") (pinfunction "2_2") (pintype "passive"))
      (node (ref "S3") (pin "S1") (pinfunction "S_S1") (pintype "passive"))
      (node (ref "S3") (pin "S2") (pinfunction "S_S2") (pintype "passive"))
      (node (ref "S3") (pin "S3") (pinfunction "S_S3") (pintype "passive"))
      (node (ref "S4") (pin "D") (pinfunction "D_D") (pintype "passive"))
      (node (ref "U5") (pin "21") (pinfunction "SB_21") (pintype "bidirectional"))
    )
    (net (code "19") (name "M1_C") (class "Default")
      (node (ref "C21") (pin "2") (pinfunction "2_2") (pintype "passive"))
      (node (ref "S5") (pin "S1") (pinfunction "S_S1") (pintype "passive"))
      (node (ref "S5") (pin "S2") (pinfunction "S_S2") (pintype "passive"))
      (node (ref "S5") (pin "S3") (pinfunction "S_S3") (pintype "passive"))
      (node (ref "S6") (pin "D") (pinfunction "D_D") (pintype "passive"))
      (node (ref "U5") (pin "16") (pinfunction "SC_16") (pintype "bidirectional"))
    )
    (net (code "20") (name "M1_DIAG") (class "Default")
      (node (ref "U1") (pin "25") (pinfunction "PC5_25") (pintype "bidirectional"))
      (node (ref "U5") (pin "5") (pinfunction "DIAG_5") (pintype "bidirectional"))
    )
    (net (code "21") (name "M1_LSS") (class "Default")
      (node (ref "R8") (pin "2") (pinfunction "2_2") (pintype "passive"))
      (node (ref "R9") (pin "2") (pinfunction "2_2") (pintype "passive"))
      (node (ref "S2") (pin "S1") (pinfunction "S_S1") (pintype "passive"))
      (node (ref "S2") (pin "S2") (pinfunction "S_S2") (pintype "passive"))
      (node (ref "S2") (pin "S3") (pinfunction "S_S3") (pintype "passive"))
      (node (ref "S4") (pin "S1") (pinfunction "S_S1") (pintype "passive"))
      (node (ref "S4") (pin "S2") (pinfunction "S_S2") (pintype "passive"))
      (node (ref "S4") (pin "S3") (pinfunction "S_S3") (pintype "passive"))
      (node (ref "S6") (pin "S1") (pinfunction "S_S1") (pintype "passive"))
      (node (ref "S6") (pin "S2") (pinfunction "S_S2") (pintype "passive"))
      (node (ref "S6") (pin "S3") (pinfunction "S_S3") (pintype "passive"))
      (node (ref "U5") (pin "13") (pinfunction "CSP_13") (pintype "bidirectional"))
      (node (ref "U5") (pin "14") (pinfunction "LSS_14") (pintype "bidirectional"))
    )
    (net (code "22") (name "M1_MISO") (class "Default")
      (node (ref "U1") (pin "35") (pinfunction "PB14_35") (pintype "bidirectional"))
      (node (ref "U5") (pin "8") (pinfunction "SDO_8") (pintype "bidirectional"))
    )
    (net (code "23") (name "M1_MOSI") (class "Default")
      (node (ref "U1") (pin "36") (pinfunction "PB15_36") (pintype "bidirectional"))
      (node (ref "U5") (pin "10") (pinfunction "SDI_10") (pintype "input"))
    )
    (net (code "24") (name "M1_NSS") (class "Default")
      (node (ref "U1") (pin "37") (pinfunction "PC6_37") (pintype "bidirectional"))
      (node (ref "U5") (pin "11") (pinfunction "STRN_11") (pintype "input"))
    )
    (net (code "25") (name "M1_PWM") (class "Default")
      (node (ref "U1") (pin "27") (pinfunction "PB1_27") (pintype "bidirectional"))
      (node (ref "U5") (pin "6") (pinfunction "PWM_6") (pintype "input"))
    )
    (net (code "26") (name "M1_SCK") (class "Default")
      (node (ref "U1") (pin "34") (pinfunction "PB13_34") (pintype "bidirectional"))
      (node (ref "U5") (pin "9") (pinfunction "SCK_9") (pintype "input"))
    )
    (net (code "27") (name "M1_TACHO") (class "Default")
      (node (ref "U1") (pin "30") (pinfunction "PB11_30") (pintype "bidirectional"))
      (node (ref "U5") (pin "7") (pinfunction "TACHO_7") (pintype "bidirectional"))
    )
    (net (code "28") (name "M2_A") (class "Default")
      (node (ref "C24") (pin "2") (pinfunction "2_2") (pintype "passive"))
      (node (ref "S7") (pin "S1") (pinfunction "S_S1") (pintype "passive"))
      (node (ref "S7") (pin "S2") (pinfunction "S_S2") (pintype "passive"))
      (node (ref "S7") (pin "S3") (pinfunction "S_S3") (pintype "passive"))
      (node (ref "S8") (pin "D") (pinfunction "D_D") (pintype "passive"))
      (node (ref "U6") (pin "25") (pinfunction "SA_25") (pintype "bidirectional"))
    )
    (net (code "29") (name "M2_B") (class "Default")
      (node (ref "C25") (pin "2") (pinfunction "2_2") (pintype "passive"))
      (node (ref "S10") (pin "D") (pinfunction "D_D") (pintype "passive"))
      (node (ref "S9") (pin "S1") (pinfunction "S_S1") (pintype "passive"))
      (node (ref "S9") (pin "S2") (pinfunction "S_S2") (pintype "passive"))
      (node (ref "S9") (pin "S3") (pinfunction "S_S3") (pintype "passive"))
      (node (ref "U6") (pin "21") (pinfunction "SB_21") (pintype "bidirectional"))
    )
    (net (code "30") (name "M2_C") (class "Default")
      (node (ref "C26") (pin "2") (pinfunction "2_2") (pintype "passive"))
      (node (ref "S11") (pin "S1") (pinfunction "S_S1") (pintype "passive"))
      (node (ref "S11") (pin "S2") (pinfunction "S_S2") (pintype "passive"))
      (node (ref "S11") (pin "S3") (pinfunction "S_S3") (pintype "passive"))
      (node (ref "S12") (pin "D") (pinfunction "D_D") (pintype "passive"))
      (node (ref "U6") (pin "16") (pinfunction "SC_16") (pintype "bidirectional"))
    )
    (net (code "31") (name "M2_DIAG") (class "Default")
      (node (ref "U1") (pin "38") (pinfunction "PC7_38") (pintype "bidirectional"))
      (node (ref "U6") (pin "5") (pinfunction "DIAG_5") (pintype "bidirectional"))
    )
    (net (code "32") (name "M2_LSS") (class "Default")
      (node (ref "R11") (pin "2") (pinfunction "2_2") (pintype "passive"))
      (node (ref "R13") (pin "2") (pinfunction "2_2") (pintype "passive"))
      (node (ref "S10") (pin "S1") (pinfunction "S_S1") (pintype "passive"))
      (node (ref "S10") (pin "S2") (pinfunction "S_S2") (pintype "passive"))
      (node (ref "S10") (pin "S3") (pinfunction "S_S3") (pintype "passive"))
      (node (ref "S12") (pin "S1") (pinfunction "S_S1") (pintype "passive"))
      (node (ref "S12") (pin "S2") (pinfunction "S_S2") (pintype "passive"))
      (node (ref "S12") (pin "S3") (pinfunction "S_S3") (pintype "passive"))
      (node (ref "S8") (pin "S1") (pinfunction "S_S1") (pintype "passive"))
      (node (ref "S8") (pin "S2") (pinfunction "S_S2") (pintype "passive"))
      (node (ref "S8") (pin "S3") (pinfunction "S_S3") (pintype "passive"))
      (node (ref "U6") (pin "13") (pinfunction "CSP_13") (pintype "bidirectional"))
      (node (ref "U6") (pin "14") (pinfunction "LSS_14") (pintype "bidirectional"))
    )
    (net (code "33") (name "M2_MISO") (class "Default")
      (node (ref "U1") (pin "52") (pinfunction "PC11_52") (pintype "bidirectional"))
      (node (ref "U6") (pin "8") (pinfunction "SDO_8") (pintype "bidirectional"))
    )
    (net (code "34") (name "M2_MOSI") (class "Default")
      (node (ref "U1") (pin "53") (pinfunction "PC12_53") (pintype "bidirectional"))
      (node (ref "U6") (pin "10") (pinfunction "SDI_10") (pintype "input"))
    )
    (net (code "35") (name "M2_NSS") (class "Default")
      (node (ref "U1") (pin "54") (pinfunction "PD2_54") (pintype "bidirectional"))
      (node (ref "U6") (pin "11") (pinfunction "STRN_11") (pintype "input"))
    )
    (net (code "36") (name "M2_PWM") (class "Default")
      (node (ref "U1") (pin "39") (pinfunction "PC8_39") (pintype "bidirectional"))
      (node (ref "U6") (pin "6") (pinfunction "PWM_6") (pintype "input"))
    )
    (net (code "37") (name "M2_SCK") (class "Default")
      (node (ref "U1") (pin "51") (pinfunction "PC10_51") (pintype "bidirectional"))
      (node (ref "U6") (pin "9") (pinfunction "SCK_9") (pintype "input"))
    )
    (net (code "38") (name "M2_TACHO") (class "Default")
      (node (ref "U1") (pin "50") (pinfunction "PA15_50") (pintype "bidirectional"))
      (node (ref "U6") (pin "7") (pinfunction "TACHO_7") (pintype "bidirectional"))
    )
    (net (code "39") (name "MPU_SCL") (class "Default")
      (node (ref "U1") (pin "61") (pinfunction "PB8_61") (pintype "bidirectional"))
      (node (ref "U3") (pin "23") (pinfunction "SCL_23") (pintype "bidirectional"))
    )
    (net (code "40") (name "MPU_SDA") (class "Default")
      (node (ref "U1") (pin "59") (pinfunction "PB7_59") (pintype "bidirectional"))
      (node (ref "U3") (pin "24") (pinfunction "SDA_24") (pintype "bidirectional"))
    )
    (net (code "41") (name "Net-(C3-Pad1)") (class "Default")
      (node (ref "C3") (pin "1") (pinfunction "1_1") (pintype "passive"))
      (node (ref "FB2") (pin "2") (pinfunction "2_2") (pintype "passive"))
      (node (ref "L1") (pin "1") (pinfunction "1_1") (pintype "passive"))
    )
    (net (code "42") (name "Net-(C6-Pad1)") (class "Default")
      (node (ref "C6") (pin "1") (pinfunction "1_1") (pintype "passive"))
      (node (ref "U$1") (pin "CP2") (pinfunction "CP2_CP2") (pintype "bidirectional"))
    )
    (net (code "43") (name "Net-(C6-Pad2)") (class "Default")
      (node (ref "C6") (pin "2") (pinfunction "2_2") (pintype "passive"))
      (node (ref "U$1") (pin "CP1") (pinfunction "CP1_CP1") (pintype "bidirectional"))
    )
    (net (code "44") (name "Net-(C7-Pad1)") (class "Default")
      (node (ref "C7") (pin "1") (pinfunction "1_1") (pintype "passive"))
      (node (ref "U$1") (pin "CP4") (pinfunction "CP4_CP4") (pintype "bidirectional"))
    )
    (net (code "45") (name "Net-(C7-Pad2)") (class "Default")
      (node (ref "C7") (pin "2") (pinfunction "2_2") (pintype "passive"))
      (node (ref "U$1") (pin "CP3") (pinfunction "CP3_CP3") (pintype "bidirectional"))
    )
    (net (code "46") (name "Net-(C8-Pad2)") (class "Default")
      (node (ref "C8") (pin "2") (pinfunction "2_2") (pintype "passive"))
      (node (ref "U$1") (pin "CP5") (pinfunction "CP5_CP5") (pintype "bidirectional"))
    )
    (net (code "47") (name "Net-(C9-Pad2)") (class "Default")
      (node (ref "C9") (pin "2") (pinfunction "2_2") (pintype "passive"))
      (node (ref "R6") (pin "2") (pinfunction "2_2") (pintype "passive"))
      (node (ref "U$1") (pin "SUMJ") (pinfunction "SUMJ_SUMJ") (pintype "bidirectional"))
    )
    (net (code "48") (name "Net-(JP1-Pad1)") (class "Default")
      (node (ref "JP1") (pin "1") (pinfunction "1_1") (pintype "passive"))
      (node (ref "R3") (pin "1") (pinfunction "1_1") (pintype "passive"))
    )
    (net (code "49") (name "Net-(JP3-Pad1)") (class "Default")
      (node (ref "JP3") (pin "1") (pinfunction "1_1") (pintype "passive"))
      (node (ref "R2") (pin "1") (pinfunction "1_1") (pintype "passive"))
    )
    (net (code "50") (name "Net-(LDBT-A)") (class "Default")
      (node (ref "LDBT") (pin "+") (pinfunction "A_+") (pintype "passive"))
      (node (ref "R5") (pin "1") (pinfunction "1_1") (pintype "passive"))
    )
    (net (code "51") (name "Net-(LEDB-A)") (class "Default")
      (node (ref "LEDB") (pin "+") (pinfunction "A_+") (pintype "passive"))
      (node (ref "R1") (pin "1") (pinfunction "1_1") (pintype "passive"))
    )
    (net (code "52") (name "Net-(LEDY-A)") (class "Default")
      (node (ref "LEDY") (pin "+") (pinfunction "A_+") (pintype "passive"))
      (node (ref "R4") (pin "1") (pinfunction "1_1") (pintype "passive"))
    )
    (net (code "53") (name "Net-(U$2-PIO5)") (class "Default")
      (node (ref "R5") (pin "2") (pinfunction "2_2") (pintype "passive"))
      (node (ref "U$2") (pin "21") (pinfunction "PIO5_21") (pintype "bidirectional"))
    )
    (net (code "54") (name "Net-(U1H-PD0{slash}OSC<=)") (class "Default")
      (node (ref "U1") (pin "5") (pinfunction "PD0/OSC<=_5") (pintype "bidirectional"))
      (node (ref "X1") (pin "1") (pinfunction "P$1_1") (pintype "bidirectional"))
    )
    (net (code "55") (name "Net-(U1H-PD1{slash}OSC=>)") (class "Default")
      (node (ref "U1") (pin "6") (pinfunction "PD1/OSC=>_6") (pintype "bidirectional"))
      (node (ref "X1") (pin "3") (pinfunction "P$3_3") (pintype "bidirectional"))
    )
    (net (code "56") (name "Net-(U1I-VSS_1)") (class "Default")
      (node (ref "U1") (pin "31") (pinfunction "VSS_1_31") (pintype "power_in"))
      (node (ref "VCAP1") (pin "1") (pinfunction "1_1") (pintype "passive"))
    )
    (net (code "57") (name "Net-(U1I-VSS_2)") (class "Default")
      (node (ref "U1") (pin "47") (pinfunction "VSS_2_47") (pintype "power_in"))
      (node (ref "VCAP2") (pin "1") (pinfunction "1_1") (pintype "passive"))
    )
    (net (code "58") (name "Net-(U2-AINN)") (class "Default")
      (node (ref "C11") (pin "1") (pinfunction "1_1") (pintype "passive"))
      (node (ref "U2") (pin "16") (pinfunction "REFOUT_16") (pintype "output"))
      (node (ref "U2") (pin "2") (pinfunction "AINN_2") (pintype "input"))
    )
    (net (code "59") (name "Net-(U2-AINP)") (class "Default")
      (node (ref "C9") (pin "1") (pinfunction "1_1") (pintype "passive"))
      (node (ref "R6") (pin "1") (pinfunction "1_1") (pintype "passive"))
      (node (ref "U$1") (pin "RATEOUT") (pinfunction "RATEOUT_RATEOUT") (pintype "bidirectional"))
      (node (ref "U2") (pin "1") (pinfunction "AINP_1") (pintype "input"))
    )
    (net (code "60") (name "Net-(U2-BYPASS)") (class "Default")
      (node (ref "C12") (pin "1") (pinfunction "1_1") (pintype "passive"))
      (node (ref "U2") (pin "13") (pinfunction "BYPASS_13") (pintype "bidirectional"))
    )
    (net (code "61") (name "Net-(U2-VREFN)") (class "Default")
      (node (ref "C10") (pin "2") (pinfunction "2_2") (pintype "passive"))
      (node (ref "U2") (pin "18") (pinfunction "VREFN_18") (pintype "input"))
    )
    (net (code "62") (name "Net-(U2-VREFP)") (class "Default")
      (node (ref "C10") (pin "1") (pinfunction "1_1") (pintype "passive"))
      (node (ref "U2") (pin "17") (pinfunction "VREFP_17") (pintype "input"))
    )
    (net (code "63") (name "Net-(U3-CPOUT)") (class "Default")
      (node (ref "C13") (pin "2") (pinfunction "2_2") (pintype "passive"))
      (node (ref "U3") (pin "20") (pinfunction "CPOUT_20") (pintype "bidirectional"))
    )
    (net (code "64") (name "Net-(U3-REGOUT)") (class "Default")
      (node (ref "C14") (pin "2") (pinfunction "2_2") (pintype "passive"))
      (node (ref "U3") (pin "10") (pinfunction "REGOUT_10") (pintype "bidirectional"))
    )
    (net (code "65") (name "Net-(U4-BIAS)") (class "Default")
      (node (ref "C5") (pin "1") (pinfunction "1_1") (pintype "passive"))
      (node (ref "R7") (pin "2") (pinfunction "2_2") (pintype "passive"))
      (node (ref "U4") (pin "8") (pinfunction "BIAS_8") (pintype "bidirectional"))
    )
    (net (code "66") (name "Net-(U4-BST)") (class "Default")
      (node (ref "C2") (pin "1") (pinfunction "1_1") (pintype "passive"))
      (node (ref "U4") (pin "1") (pinfunction "BST_1") (pintype "bidirectional"))
    )
    (net (code "67") (name "Net-(U4-LX)") (class "Default")
      (node (ref "C2") (pin "2") (pinfunction "2_2") (pintype "passive"))
      (node (ref "L1") (pin "2") (pinfunction "2_2") (pintype "passive"))
      (node (ref "U4") (pin "3") (pinfunction "LX_3") (pintype "bidirectional"))
    )
    (net (code "68") (name "Net-(U4-PGOOD)") (class "Default")
      (node (ref "R7") (pin "1") (pinfunction "1_1") (pintype "passive"))
      (node (ref "U4") (pin "6") (pinfunction "PGOOD_6") (pintype "output"))
    )
    (net (code "69") (name "Net-(U5-CA)") (class "Default")
      (node (ref "C19") (pin "1") (pinfunction "1_1") (pintype "passive"))
      (node (ref "U5") (pin "26") (pinfunction "CA_26") (pintype "bidirectional"))
    )
    (net (code "70") (name "Net-(U5-CB)") (class "Default")
      (node (ref "C20") (pin "1") (pinfunction "1_1") (pintype "passive"))
      (node (ref "U5") (pin "22") (pinfunction "CB_22") (pintype "bidirectional"))
    )
    (net (code "71") (name "Net-(U5-CC)") (class "Default")
      (node (ref "C21") (pin "1") (pinfunction "1_1") (pintype "passive"))
      (node (ref "U5") (pin "17") (pinfunction "CC_17") (pintype "bidirectional"))
    )
    (net (code "72") (name "Net-(U5-CP1)") (class "Default")
      (node (ref "C17") (pin "1") (pinfunction "1_1") (pintype "passive"))
      (node (ref "U5") (pin "29") (pinfunction "CP1_29") (pintype "bidirectional"))
    )
    (net (code "73") (name "Net-(U5-CP2)") (class "Default")
      (node (ref "C17") (pin "2") (pinfunction "2_2") (pintype "passive"))
      (node (ref "U5") (pin "28") (pinfunction "CP2_28") (pintype "bidirectional"))
    )
    (net (code "74") (name "Net-(U5-GHA)") (class "Default")
      (node (ref "S1") (pin "G") (pinfunction "G_G") (pintype "passive"))
      (node (ref "U5") (pin "24") (pinfunction "GHA_24") (pintype "bidirectional"))
    )
    (net (code "75") (name "Net-(U5-GHB)") (class "Default")
      (node (ref "S3") (pin "G") (pinfunction "G_G") (pintype "passive"))
      (node (ref "U5") (pin "20") (pinfunction "GHB_20") (pintype "bidirectional"))
    )
    (net (code "76") (name "Net-(U5-GHC)") (class "Default")
      (node (ref "S5") (pin "G") (pinfunction "G_G") (pintype "passive"))
      (node (ref "U5") (pin "18") (pinfunction "GHC_18") (pintype "bidirectional"))
    )
    (net (code "77") (name "Net-(U5-GLA)") (class "Default")
      (node (ref "S2") (pin "G") (pinfunction "G_G") (pintype "passive"))
      (node (ref "U5") (pin "23") (pinfunction "GLA_23") (pintype "bidirectional"))
    )
    (net (code "78") (name "Net-(U5-GLB)") (class "Default")
      (node (ref "S4") (pin "G") (pinfunction "G_G") (pintype "passive"))
      (node (ref "U5") (pin "19") (pinfunction "GLB_19") (pintype "bidirectional"))
    )
    (net (code "79") (name "Net-(U5-GLC)") (class "Default")
      (node (ref "S6") (pin "G") (pinfunction "G_G") (pintype "passive"))
      (node (ref "U5") (pin "15") (pinfunction "GLC_15") (pintype "bidirectional"))
    )
    (net (code "80") (name "Net-(U5-RESETN)") (class "Default")
      (node (ref "R10") (pin "1") (pinfunction "1_1") (pintype "passive"))
      (node (ref "U5") (pin "2") (pinfunction "RESETN_2") (pintype "input"))
    )
    (net (code "81") (name "Net-(U5-VREG)") (class "Default")
      (node (ref "C18") (pin "1") (pinfunction "1_1") (pintype "passive"))
      (node (ref "U5") (pin "27") (pinfunction "VREG_27") (pintype "bidirectional"))
    )
    (net (code "82") (name "Net-(U6-CA)") (class "Default")
      (node (ref "C24") (pin "1") (pinfunction "1_1") (pintype "passive"))
      (node (ref "U6") (pin "26") (pinfunction "CA_26") (pintype "bidirectional"))
    )
    (net (code "83") (name "Net-(U6-CB)") (class "Default")
      (node (ref "C25") (pin "1") (pinfunction "1_1") (pintype "passive"))
      (node (ref "U6") (pin "22") (pinfunction "CB_22") (pintype "bidirectional"))
    )
    (net (code "84") (name "Net-(U6-CC)") (class "Default")
      (node (ref "C26") (pin "1") (pinfunction "1_1") (pintype "passive"))
      (node (ref "U6") (pin "17") (pinfunction "CC_17") (pintype "bidirectional"))
    )
    (net (code "85") (name "Net-(U6-CP1)") (class "Default")
      (node (ref "C22") (pin "1") (pinfunction "1_1") (pintype "passive"))
      (node (ref "U6") (pin "29") (pinfunction "CP1_29") (pintype "bidirectional"))
    )
    (net (code "86") (name "Net-(U6-CP2)") (class "Default")
      (node (ref "C22") (pin "2") (pinfunction "2_2") (pintype "passive"))
      (node (ref "U6") (pin "28") (pinfunction "CP2_28") (pintype "bidirectional"))
    )
    (net (code "87") (name "Net-(U6-GHA)") (class "Default")
      (node (ref "S7") (pin "G") (pinfunction "G_G") (pintype "passive"))
      (node (ref "U6") (pin "24") (pinfunction "GHA_24") (pintype "bidirectional"))
    )
    (net (code "88") (name "Net-(U6-GHB)") (class "Default")
      (node (ref "S9") (pin "G") (pinfunction "G_G") (pintype "passive"))
      (node (ref "U6") (pin "20") (pinfunction "GHB_20") (pintype "bidirectional"))
    )
    (net (code "89") (name "Net-(U6-GHC)") (class "Default")
      (node (ref "S11") (pin "G") (pinfunction "G_G") (pintype "passive"))
      (node (ref "U6") (pin "18") (pinfunction "GHC_18") (pintype "bidirectional"))
    )
    (net (code "90") (name "Net-(U6-GLA)") (class "Default")
      (node (ref "S8") (pin "G") (pinfunction "G_G") (pintype "passive"))
      (node (ref "U6") (pin "23") (pinfunction "GLA_23") (pintype "bidirectional"))
    )
    (net (code "91") (name "Net-(U6-GLB)") (class "Default")
      (node (ref "S10") (pin "G") (pinfunction "G_G") (pintype "passive"))
      (node (ref "U6") (pin "19") (pinfunction "GLB_19") (pintype "bidirectional"))
    )
    (net (code "92") (name "Net-(U6-GLC)") (class "Default")
      (node (ref "S12") (pin "G") (pinfunction "G_G") (pintype "passive"))
      (node (ref "U6") (pin "15") (pinfunction "GLC_15") (pintype "bidirectional"))
    )
    (net (code "93") (name "Net-(U6-RESETN)") (class "Default")
      (node (ref "R12") (pin "1") (pinfunction "1_1") (pintype "passive"))
      (node (ref "U6") (pin "2") (pinfunction "RESETN_2") (pintype "input"))
    )
    (net (code "94") (name "Net-(U6-VREG)") (class "Default")
      (node (ref "C23") (pin "1") (pinfunction "1_1") (pintype "passive"))
      (node (ref "U6") (pin "27") (pinfunction "VREG_27") (pintype "bidirectional"))
    )
    (net (code "95") (name "SWCLK") (class "Default")
      (node (ref "TP4") (pin "TP") (pinfunction "TP_TP") (pintype "input"))
      (node (ref "U1") (pin "49") (pinfunction "PA14_49") (pintype "bidirectional"))
    )
    (net (code "96") (name "SWDIO") (class "Default")
      (node (ref "TP5") (pin "TP") (pinfunction "TP_TP") (pintype "input"))
      (node (ref "U1") (pin "46") (pinfunction "PA13_46") (pintype "bidirectional"))
    )
    (net (code "97") (name "U1_RX") (class "Default")
      (node (ref "TP2") (pin "TP") (pinfunction "TP_TP") (pintype "input"))
      (node (ref "U1") (pin "43") (pinfunction "PA10_43") (pintype "bidirectional"))
    )
    (net (code "98") (name "U1_TX") (class "Default")
      (node (ref "TP1") (pin "TP") (pinfunction "TP_TP") (pintype "input"))
      (node (ref "U1") (pin "42") (pinfunction "PA9_42") (pintype "bidirectional"))
    )
    (net (code "99") (name "V+") (class "Default")
      (node (ref "C1") (pin "1") (pinfunction "1_1") (pintype "passive"))
      (node (ref "C30") (pin "1") (pinfunction "1_1") (pintype "passive"))
      (node (ref "C31") (pin "1") (pinfunction "1_1") (pintype "passive"))
      (node (ref "C32") (pin "1") (pinfunction "1_1") (pintype "passive"))
      (node (ref "C33") (pin "1") (pinfunction "1_1") (pintype "passive"))
      (node (ref "C34") (pin "1") (pinfunction "1_1") (pintype "passive"))
      (node (ref "C35") (pin "1") (pinfunction "1_1") (pintype "passive"))
      (node (ref "C36") (pin "1") (pinfunction "1_1") (pintype "passive"))
      (node (ref "C37") (pin "1") (pinfunction "1_1") (pintype "passive"))
      (node (ref "C38") (pin "1") (pinfunction "1_1") (pintype "passive"))
      (node (ref "C39") (pin "1") (pinfunction "1_1") (pintype "passive"))
      (node (ref "C40") (pin "1") (pinfunction "1_1") (pintype "passive"))
      (node (ref "C41") (pin "1") (pinfunction "1_1") (pintype "passive"))
      (node (ref "C42") (pin "1") (pinfunction "1_1") (pintype "passive"))
      (node (ref "C43") (pin "1") (pinfunction "1_1") (pintype "passive"))
      (node (ref "C44") (pin "1") (pinfunction "1_1") (pintype "passive"))
      (node (ref "C45") (pin "1") (pinfunction "1_1") (pintype "passive"))
      (node (ref "C46") (pin "1") (pinfunction "1_1") (pintype "passive"))
      (node (ref "C47") (pin "1") (pinfunction "1_1") (pintype "passive"))
      (node (ref "C48") (pin "1") (pinfunction "1_1") (pintype "passive"))
      (node (ref "C49") (pin "1") (pinfunction "1_1") (pintype "passive"))
      (node (ref "C50") (pin "1") (pinfunction "1_1") (pintype "passive"))
      (node (ref "C51") (pin "1") (pinfunction "1_1") (pintype "passive"))
      (node (ref "C52") (pin "1") (pinfunction "1_1") (pintype "passive"))
      (node (ref "C53") (pin "1") (pinfunction "1_1") (pintype "passive"))
      (node (ref "C54") (pin "1") (pinfunction "1_1") (pintype "passive"))
      (node (ref "C55") (pin "1") (pinfunction "1_1") (pintype "passive"))
      (node (ref "C56") (pin "1") (pinfunction "1_1") (pintype "passive"))
      (node (ref "C57") (pin "1") (pinfunction "1_1") (pintype "passive"))
      (node (ref "C58") (pin "1") (pinfunction "1_1") (pintype "passive"))
      (node (ref "C59") (pin "1") (pinfunction "1_1") (pintype "passive"))
      (node (ref "C60") (pin "1") (pinfunction "1_1") (pintype "passive"))
      (node (ref "C61") (pin "1") (pinfunction "1_1") (pintype "passive"))
      (node (ref "C62") (pin "1") (pinfunction "1_1") (pintype "passive"))
      (node (ref "C63") (pin "1") (pinfunction "1_1") (pintype "passive"))
      (node (ref "C64") (pin "1") (pinfunction "1_1") (pintype "passive"))
      (node (ref "C65") (pin "1") (pinfunction "1_1") (pintype "passive"))
      (node (ref "C66") (pin "1") (pinfunction "1_1") (pintype "passive"))
      (node (ref "C67") (pin "1") (pinfunction "1_1") (pintype "passive"))
      (node (ref "C68") (pin "1") (pinfunction "1_1") (pintype "passive"))
      (node (ref "C69") (pin "1") (pinfunction "1_1") (pintype "passive"))
      (node (ref "C70") (pin "1") (pinfunction "1_1") (pintype "passive"))
      (node (ref "C71") (pin "1") (pinfunction "1_1") (pintype "passive"))
      (node (ref "C72") (pin "1") (pinfunction "1_1") (pintype "passive"))
      (node (ref "C73") (pin "1") (pinfunction "1_1") (pintype "passive"))
      (node (ref "R10") (pin "2") (pinfunction "2_2") (pintype "passive"))
      (node (ref "R12") (pin "2") (pinfunction "2_2") (pintype "passive"))
      (node (ref "S1") (pin "D") (pinfunction "D_D") (pintype "passive"))
      (node (ref "S11") (pin "D") (pinfunction "D_D") (pintype "passive"))
      (node (ref "S3") (pin "D") (pinfunction "D_D") (pintype "passive"))
      (node (ref "S5") (pin "D") (pinfunction "D_D") (pintype "passive"))
      (node (ref "S7") (pin "D") (pinfunction "D_D") (pintype "passive"))
      (node (ref "S9") (pin "D") (pinfunction "D_D") (pintype "passive"))
      (node (ref "U4") (pin "10") (pinfunction "EN_10") (pintype "input"))
      (node (ref "U4") (pin "2") (pinfunction "SUP_2") (pintype "bidirectional"))
      (node (ref "U5") (pin "1") (pinfunction "VBRG_1") (pintype "bidirectional"))
      (node (ref "U5") (pin "32") (pinfunction "VBB_32") (pintype "power_in"))
      (node (ref "U6") (pin "1") (pinfunction "VBRG_1") (pintype "bidirectional"))
      (node (ref "U6") (pin "32") (pinfunction "VBB_32") (pintype "power_in"))
    )
    (net (code "100") (name "V-") (class "Default")
      (node (ref "C1") (pin "2") (pinfunction "2_2") (pintype "passive"))
      (node (ref "C3") (pin "2") (pinfunction "2_2") (pintype "passive"))
      (node (ref "C30") (pin "2") (pinfunction "2_2") (pintype "passive"))
      (node (ref "C31") (pin "2") (pinfunction "2_2") (pintype "passive"))
      (node (ref "C32") (pin "2") (pinfunction "2_2") (pintype "passive"))
      (node (ref "C33") (pin "2") (pinfunction "2_2") (pintype "passive"))
      (node (ref "C34") (pin "2") (pinfunction "2_2") (pintype "passive"))
      (node (ref "C35") (pin "2") (pinfunction "2_2") (pintype "passive"))
      (node (ref "C36") (pin "2") (pinfunction "2_2") (pintype "passive"))
      (node (ref "C37") (pin "2") (pinfunction "2_2") (pintype "passive"))
      (node (ref "C38") (pin "2") (pinfunction "2_2") (pintype "passive"))
      (node (ref "C39") (pin "2") (pinfunction "2_2") (pintype "passive"))
      (node (ref "C4") (pin "2") (pinfunction "2_2") (pintype "passive"))
      (node (ref "C40") (pin "2") (pinfunction "2_2") (pintype "passive"))
      (node (ref "C41") (pin "2") (pinfunction "2_2") (pintype "passive"))
      (node (ref "C42") (pin "2") (pinfunction "2_2") (pintype "passive"))
      (node (ref "C43") (pin "2") (pinfunction "2_2") (pintype "passive"))
      (node (ref "C44") (pin "2") (pinfunction "2_2") (pintype "passive"))
      (node (ref "C45") (pin "2") (pinfunction "2_2") (pintype "passive"))
      (node (ref "C46") (pin "2") (pinfunction "2_2") (pintype "passive"))
      (node (ref "C47") (pin "2") (pinfunction "2_2") (pintype "passive"))
      (node (ref "C48") (pin "2") (pinfunction "2_2") (pintype "passive"))
      (node (ref "C49") (pin "2") (pinfunction "2_2") (pintype "passive"))
      (node (ref "C50") (pin "2") (pinfunction "2_2") (pintype "passive"))
      (node (ref "C51") (pin "2") (pinfunction "2_2") (pintype "passive"))
      (node (ref "C52") (pin "2") (pinfunction "2_2") (pintype "passive"))
      (node (ref "C53") (pin "2") (pinfunction "2_2") (pintype "passive"))
      (node (ref "C54") (pin "2") (pinfunction "2_2") (pintype "passive"))
      (node (ref "C55") (pin "2") (pinfunction "2_2") (pintype "passive"))
      (node (ref "C56") (pin "2") (pinfunction "2_2") (pintype "passive"))
      (node (ref "C57") (pin "2") (pinfunction "2_2") (pintype "passive"))
      (node (ref "C58") (pin "2") (pinfunction "2_2") (pintype "passive"))
      (node (ref "C59") (pin "2") (pinfunction "2_2") (pintype "passive"))
      (node (ref "C60") (pin "2") (pinfunction "2_2") (pintype "passive"))
      (node (ref "C61") (pin "2") (pinfunction "2_2") (pintype "passive"))
      (node (ref "C62") (pin "2") (pinfunction "2_2") (pintype "passive"))
      (node (ref "C63") (pin "2") (pinfunction "2_2") (pintype "passive"))
      (node (ref "C64") (pin "2") (pinfunction "2_2") (pintype "passive"))
      (node (ref "C65") (pin "2") (pinfunction "2_2") (pintype "passive"))
      (node (ref "C66") (pin "2") (pinfunction "2_2") (pintype "passive"))
      (node (ref "C67") (pin "2") (pinfunction "2_2") (pintype "passive"))
      (node (ref "C68") (pin "2") (pinfunction "2_2") (pintype "passive"))
      (node (ref "C69") (pin "2") (pinfunction "2_2") (pintype "passive"))
      (node (ref "C70") (pin "2") (pinfunction "2_2") (pintype "passive"))
      (node (ref "C71") (pin "2") (pinfunction "2_2") (pintype "passive"))
      (node (ref "C72") (pin "2") (pinfunction "2_2") (pintype "passive"))
      (node (ref "C73") (pin "2") (pinfunction "2_2") (pintype "passive"))
      (node (ref "R11") (pin "1") (pinfunction "1_1") (pintype "passive"))
      (node (ref "R13") (pin "1") (pinfunction "1_1") (pintype "passive"))
      (node (ref "R8") (pin "1") (pinfunction "1_1") (pintype "passive"))
      (node (ref "R9") (pin "1") (pinfunction "1_1") (pintype "passive"))
      (node (ref "U4") (pin "4") (pinfunction "PGND_4") (pintype "power_in"))
      (node (ref "U4") (pin "PAD") (pinfunction "PAD_PAD") (pintype "power_in"))
      (node (ref "U5") (pin "12") (pinfunction "CSM_12") (pintype "bidirectional"))
      (node (ref "U6") (pin "12") (pinfunction "CSM_12") (pintype "bidirectional"))
    )
    (net (code "101") (name "VDD") (class "Default")
      (node (ref "C15") (pin "1") (pinfunction "1_1") (pintype "passive"))
      (node (ref "C_HALL") (pin "1") (pinfunction "1_1") (pintype "passive"))
      (node (ref "C_MPU") (pin "2") (pinfunction "2_2") (pintype "passive"))
      (node (ref "C_V1") (pin "1") (pinfunction "1_1") (pintype "passive"))
      (node (ref "C_V2") (pin "1") (pinfunction "1_1") (pintype "passive"))
      (node (ref "C_V3") (pin "1") (pinfunction "1_1") (pintype "passive"))
      (node (ref "C_V4") (pin "1") (pinfunction "1_1") (pintype "passive"))
      (node (ref "C_VA") (pin "1") (pinfunction "1_1") (pintype "passive"))
      (node (ref "IC1") (pin "3") (pinfunction "OUT_3") (pintype "passive"))
      (node (ref "LDBT") (pin "-") (pinfunction "C_-") (pintype "passive"))
      (node (ref "U$2") (pin "11") (pinfunction "VDD_11") (pintype "bidirectional"))
      (node (ref "U1") (pin "1") (pinfunction "VBAT_1") (pintype "power_in"))
      (node (ref "U1") (pin "13") (pinfunction "VDDA_13") (pintype "power_in"))
      (node (ref "U1") (pin "19") (pinfunction "VDD_4_19") (pintype "power_in"))
      (node (ref "U1") (pin "32") (pinfunction "VDD_1_32") (pintype "power_in"))
      (node (ref "U1") (pin "48") (pinfunction "VDD_2_48") (pintype "power_in"))
      (node (ref "U1") (pin "64") (pinfunction "VDD_3_64") (pintype "power_in"))
      (node (ref "U2") (pin "15") (pinfunction "DVDD_15") (pintype "power_in"))
      (node (ref "U3") (pin "13") (pinfunction "VDD_13") (pintype "bidirectional"))
      (node (ref "U3") (pin "8") (pinfunction "VLOGIC_8") (pintype "bidirectional"))
      (node (ref "U5") (pin "3") (pinfunction "REF_3") (pintype "bidirectional"))
      (node (ref "U5") (pin "4") (pinfunction "VDD_4") (pintype "power_in"))
      (node (ref "U6") (pin "3") (pinfunction "REF_3") (pintype "bidirectional"))
      (node (ref "U6") (pin "4") (pinfunction "VDD_4") (pintype "power_in"))
      (node (ref "U7") (pin "1") (pinfunction "VDD_1") (pintype "power_in"))
    )
    (net (code "102") (name "unconnected-(U$1-PadNC)") (class "Default")
      (node (ref "U$1") (pin "NC") (pinfunction "NC_NC") (pintype "bidirectional"))
    )
    (net (code "103") (name "unconnected-(U$1-PadST1)") (class "Default")
      (node (ref "U$1") (pin "ST1") (pinfunction "ST1_ST1") (pintype "bidirectional"))
    )
    (net (code "104") (name "unconnected-(U$1-PadST2)") (class "Default")
      (node (ref "U$1") (pin "ST2") (pinfunction "ST2_ST2") (pintype "bidirectional"))
    )
    (net (code "105") (name "unconnected-(U$1-PadTEMP)") (class "Default")
      (node (ref "U$1") (pin "TEMP") (pinfunction "TEMP_TEMP") (pintype "bidirectional"))
    )
    (net (code "106") (name "unconnected-(U$2-AIO1-Pad35)") (class "Default")
      (node (ref "U$2") (pin "35") (pinfunction "AIO1_35") (pintype "bidirectional"))
    )
    (net (code "107") (name "unconnected-(U$2-AIO2-Pad30)") (class "Default")
      (node (ref "U$2") (pin "30") (pinfunction "AIO2_30") (pintype "bidirectional"))
    )
    (net (code "108") (name "unconnected-(U$2-GND2-Pad25)") (class "Default")
      (node (ref "U$2") (pin "25") (pinfunction "GND2_25") (pintype "bidirectional"))
    )
    (net (code "109") (name "unconnected-(U$2-GND3-Pad27)") (class "Default")
      (node (ref "U$2") (pin "27") (pinfunction "GND3_27") (pintype "bidirectional"))
    )
    (net (code "110") (name "unconnected-(U$2-NC-Pad26)") (class "Default")
      (node (ref "U$2") (pin "26") (pinfunction "NC_26") (pintype "bidirectional"))
    )
    (net (code "111") (name "unconnected-(U$2-PCMCLK-Pad7)") (class "Default")
      (node (ref "U$2") (pin "7") (pinfunction "PCMCLK_7") (pintype "bidirectional"))
    )
    (net (code "112") (name "unconnected-(U$2-PCMIN-Pad9)") (class "Default")
      (node (ref "U$2") (pin "9") (pinfunction "PCMIN_9") (pintype "bidirectional"))
    )
    (net (code "113") (name "unconnected-(U$2-PCMOUT-Pad10)") (class "Default")
      (node (ref "U$2") (pin "10") (pinfunction "PCMOUT_10") (pintype "bidirectional"))
    )
    (net (code "114") (name "unconnected-(U$2-PCMSYNC-Pad8)") (class "Default")
      (node (ref "U$2") (pin "8") (pinfunction "PCMSYNC_8") (pintype "bidirectional"))
    )
    (net (code "115") (name "unconnected-(U$2-PIO2-Pad19)") (class "Default")
      (node (ref "U$2") (pin "19") (pinfunction "PIO2_19") (pintype "bidirectional"))
    )
    (net (code "116") (name "unconnected-(U$2-PIO3-Pad20)") (class "Default")
      (node (ref "U$2") (pin "20") (pinfunction "PIO3_20") (pintype "bidirectional"))
    )
    (net (code "117") (name "unconnected-(U$2-PIO4-Pad22)") (class "Default")
      (node (ref "U$2") (pin "22") (pinfunction "PIO4_22") (pintype "bidirectional"))
    )
    (net (code "118") (name "unconnected-(U$2-PIO6-Pad3)") (class "Default")
      (node (ref "U$2") (pin "3") (pinfunction "PIO6_3") (pintype "bidirectional"))
    )
    (net (code "119") (name "unconnected-(U$2-PIO7-Pad4)") (class "Default")
      (node (ref "U$2") (pin "4") (pinfunction "PIO7_4") (pintype "bidirectional"))
    )
    (net (code "120") (name "unconnected-(U$2-PIO8-Pad31)") (class "Default")
      (node (ref "U$2") (pin "31") (pinfunction "PIO8_31") (pintype "bidirectional"))
    )
    (net (code "121") (name "unconnected-(U$2-PIO9-Pad32)") (class "Default")
      (node (ref "U$2") (pin "32") (pinfunction "PIO9_32") (pintype "bidirectional"))
    )
    (net (code "122") (name "unconnected-(U$2-PIO10-Pad33)") (class "Default")
      (node (ref "U$2") (pin "33") (pinfunction "PIO10_33") (pintype "bidirectional"))
    )
    (net (code "123") (name "unconnected-(U$2-PIO11-Pad34)") (class "Default")
      (node (ref "U$2") (pin "34") (pinfunction "PIO11_34") (pintype "bidirectional"))
    )
    (net (code "124") (name "unconnected-(U$2-RESET-Pad5)") (class "Default")
      (node (ref "U$2") (pin "5") (pinfunction "RESET_5") (pintype "bidirectional"))
    )
    (net (code "125") (name "unconnected-(U$2-SPICLK-Pad6)") (class "Default")
      (node (ref "U$2") (pin "6") (pinfunction "SPICLK_6") (pintype "bidirectional"))
    )
    (net (code "126") (name "unconnected-(U$2-SPICSB-Pad23)") (class "Default")
      (node (ref "U$2") (pin "23") (pinfunction "SPICSB_23") (pintype "bidirectional"))
    )
    (net (code "127") (name "unconnected-(U$2-SPIMISO-Pad24)") (class "Default")
      (node (ref "U$2") (pin "24") (pinfunction "SPIMISO_24") (pintype "bidirectional"))
    )
    (net (code "128") (name "unconnected-(U$2-SPIMOSI-Pad2)") (class "Default")
      (node (ref "U$2") (pin "2") (pinfunction "SPIMOSI_2") (pintype "bidirectional"))
    )
    (net (code "129") (name "unconnected-(U$2-USBD+-Pad17)") (class "Default")
      (node (ref "U$2") (pin "17") (pinfunction "USBD+_17") (pintype "bidirectional"))
    )
    (net (code "130") (name "unconnected-(U$2-USBD--Pad18)") (class "Default")
      (node (ref "U$2") (pin "18") (pinfunction "USBD-_18") (pintype "bidirectional"))
    )
    (net (code "131") (name "unconnected-(U1B-PA8-Pad41)") (class "Default")
      (node (ref "U1") (pin "41") (pinfunction "PA8_41") (pintype "bidirectional"))
    )
    (net (code "132") (name "unconnected-(U1B-PA11-Pad44)") (class "Default")
      (node (ref "U1") (pin "44") (pinfunction "PA11_44") (pintype "bidirectional"))
    )
    (net (code "133") (name "unconnected-(U1B-PA12-Pad45)") (class "Default")
      (node (ref "U1") (pin "45") (pinfunction "PA12_45") (pintype "bidirectional"))
    )
    (net (code "134") (name "unconnected-(U1D-PB9-Pad62)") (class "Default")
      (node (ref "U1") (pin "62") (pinfunction "PB9_62") (pintype "bidirectional"))
    )
    (net (code "135") (name "unconnected-(U1E-PB4-Pad56)") (class "Default")
      (node (ref "U1") (pin "56") (pinfunction "PB4_56") (pintype "bidirectional"))
    )
    (net (code "136") (name "unconnected-(U1E-PB5-Pad57)") (class "Default")
      (node (ref "U1") (pin "57") (pinfunction "PB5_57") (pintype "bidirectional"))
    )
    (net (code "137") (name "unconnected-(U1E-PB6-Pad58)") (class "Default")
      (node (ref "U1") (pin "58") (pinfunction "PB6_58") (pintype "bidirectional"))
    )
    (net (code "138") (name "unconnected-(U1F-PC9-Pad40)") (class "Default")
      (node (ref "U1") (pin "40") (pinfunction "PC9_40") (pintype "bidirectional"))
    )
    (net (code "139") (name "unconnected-(U1F-PC13-Pad2)") (class "Default")
      (node (ref "U1") (pin "2") (pinfunction "PC13_2") (pintype "bidirectional"))
    )
    (net (code "140") (name "unconnected-(U1F-PC14-Pad3)") (class "Default")
      (node (ref "U1") (pin "3") (pinfunction "PC14_3") (pintype "bidirectional"))
    )
    (net (code "141") (name "unconnected-(U1F-PC15-Pad4)") (class "Default")
      (node (ref "U1") (pin "4") (pinfunction "PC15_4") (pintype "bidirectional"))
    )
    (net (code "142") (name "unconnected-(U1G-PC0-Pad8)") (class "Default")
      (node (ref "U1") (pin "8") (pinfunction "PC0_8") (pintype "bidirectional"))
    )
    (net (code "143") (name "unconnected-(U1G-PC1-Pad9)") (class "Default")
      (node (ref "U1") (pin "9") (pinfunction "PC1_9") (pintype "bidirectional"))
    )
    (net (code "144") (name "unconnected-(U1G-PC2-Pad10)") (class "Default")
      (node (ref "U1") (pin "10") (pinfunction "PC2_10") (pintype "bidirectional"))
    )
    (net (code "145") (name "unconnected-(U1G-PC3-Pad11)") (class "Default")
      (node (ref "U1") (pin "11") (pinfunction "PC3_11") (pintype "bidirectional"))
    )
    (net (code "146") (name "unconnected-(U2-SYNCOUT-Pad5)") (class "Default")
      (node (ref "U2") (pin "5") (pinfunction "SYNCOUT_5") (pintype "output"))
    )
    (net (code "147") (name "unconnected-(U2-XTAL2-Pad12)") (class "Default")
      (node (ref "U2") (pin "12") (pinfunction "XTAL2_12") (pintype "bidirectional"))
    )
    (net (code "148") (name "unconnected-(U2-~{DRDY}-Pad10)") (class "Default")
      (node (ref "U2") (pin "10") (pinfunction "~{DRDY}_10") (pintype "output"))
    )
    (net (code "149") (name "unconnected-(U2-~{RESET}-Pad3)") (class "Default")
      (node (ref "U2") (pin "3") (pinfunction "~{RESET}_3") (pintype "input"))
    )
    (net (code "150") (name "unconnected-(U3-INT-Pad12)") (class "Default")
      (node (ref "U3") (pin "12") (pinfunction "INT_12") (pintype "bidirectional"))
    )
    (net (code "151") (name "unconnected-(U5-PadPAD)") (class "Default")
      (node (ref "U5") (pin "PAD") (pinfunction "PAD_PAD") (pintype "bidirectional"))
    )
    (net (code "152") (name "unconnected-(U6-PadPAD)") (class "Default")
      (node (ref "U6") (pin "PAD") (pinfunction "PAD_PAD") (pintype "bidirectional"))
    )
    (net (code "153") (name "~{RESET}") (class "Default")
      (node (ref "C_RST") (pin "1") (pinfunction "1_1") (pintype "passive"))
      (node (ref "TP6") (pin "TP") (pinfunction "TP_TP") (pintype "input"))
      (node (ref "U1") (pin "7") (pinfunction "NRST_7") (pintype "input"))
    )
  )
)
